# NEW_MEIN.net
KiCad netlist of a schematic drawn in EAGLE
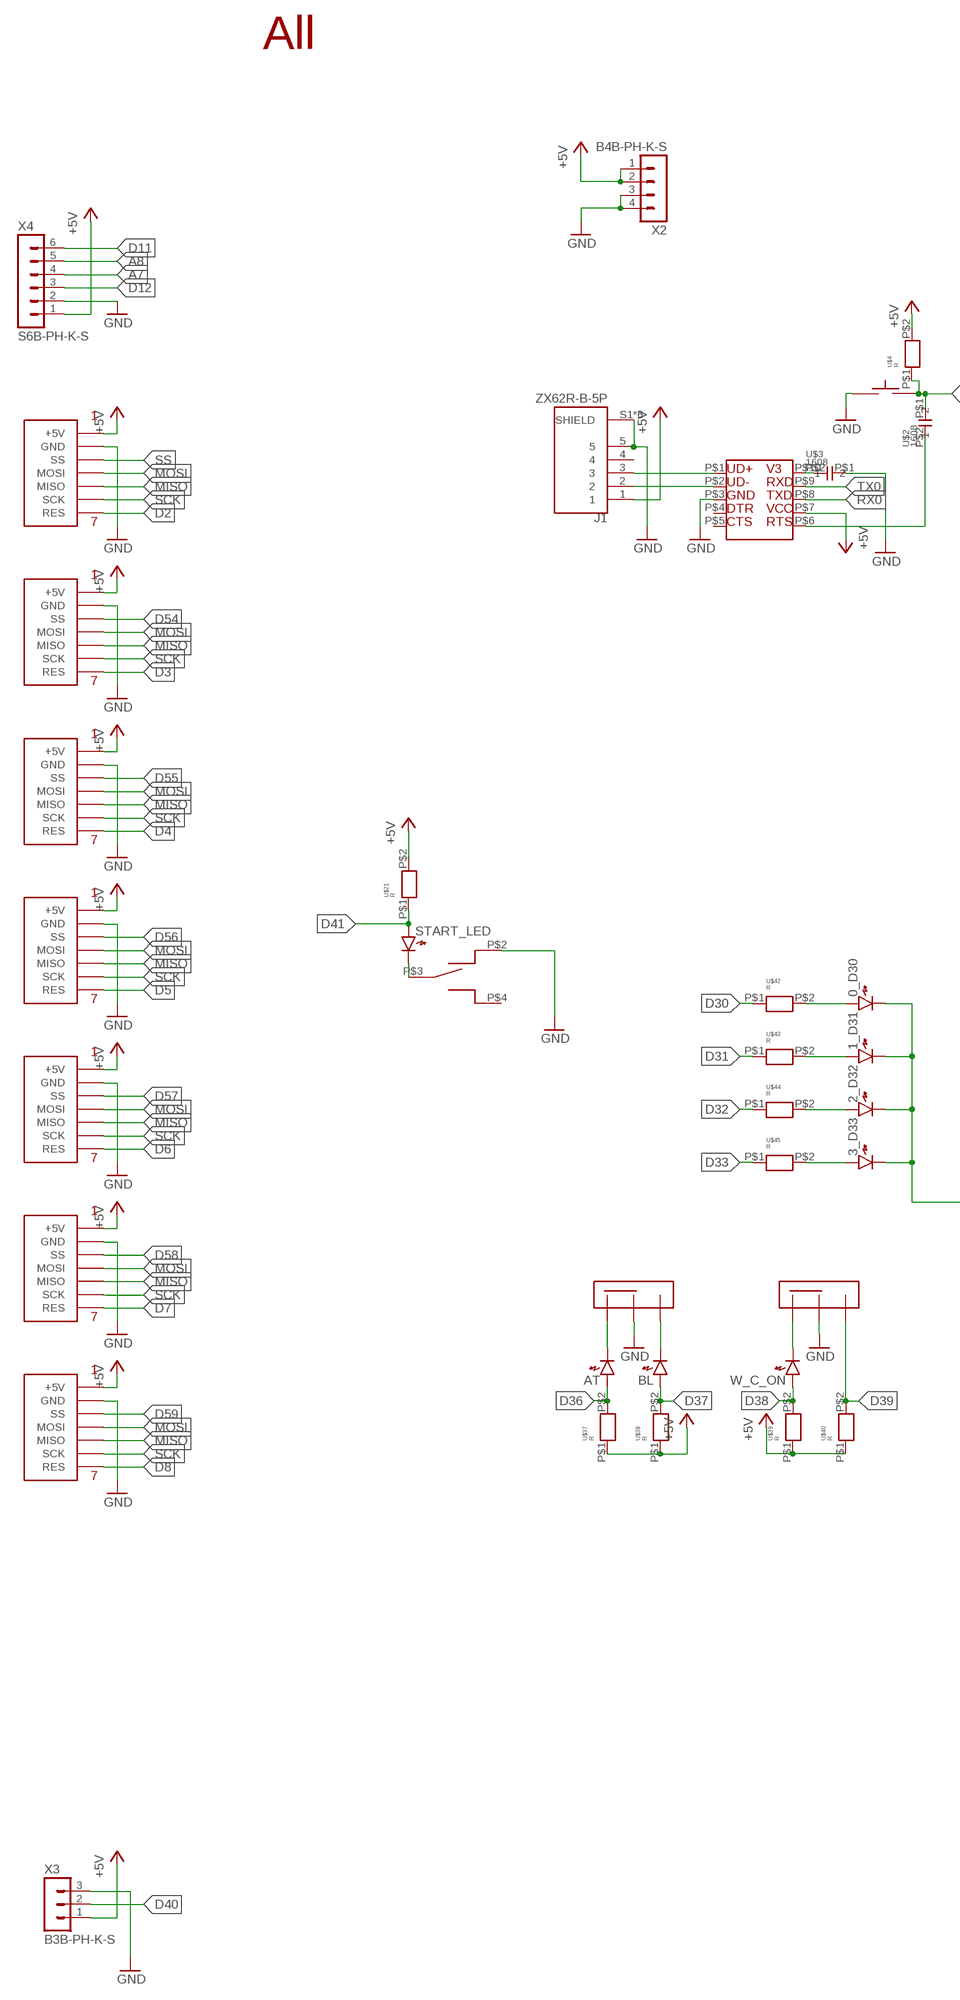
[diagram p0: schematic, sheet 1, part 1 of 2]
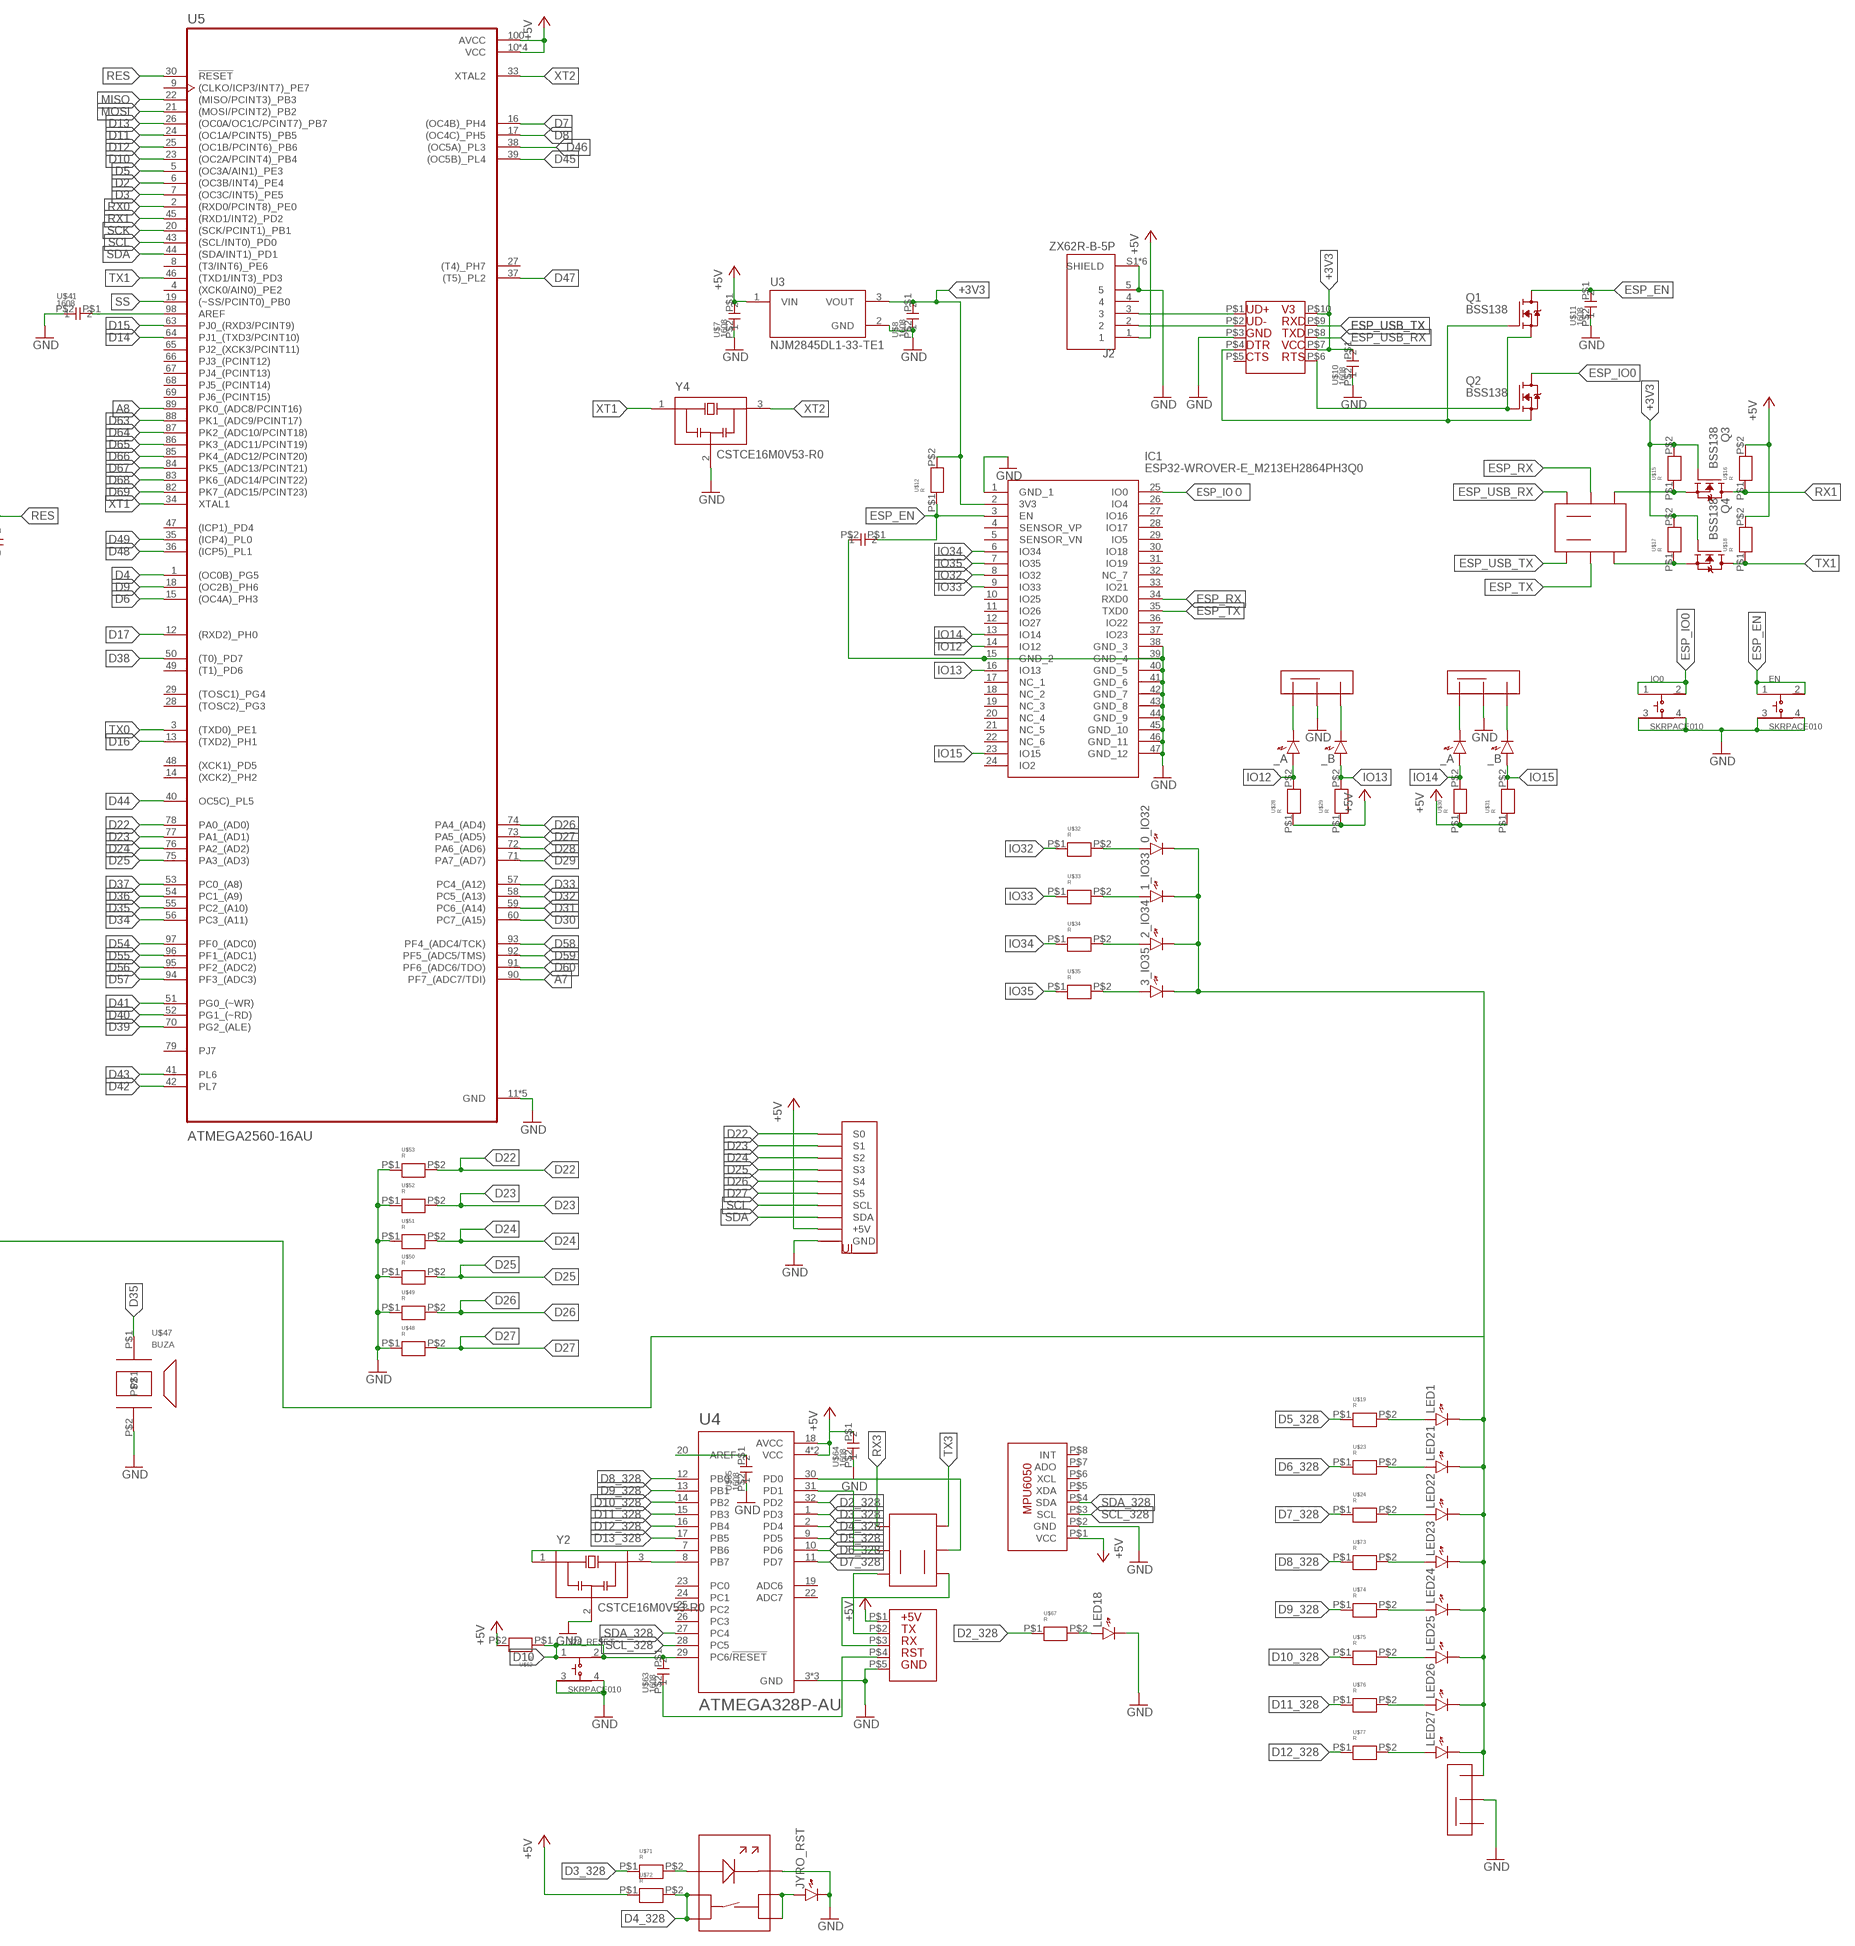
[diagram p1: schematic, sheet 1, part 2 of 2]

(export (version "E")
  (design (tool "Eeschema 10.0.6"))
  (components
    (comp (ref "0_D30")
      (value "LED1608")
      (footprint "eagle-import:LED1608")
      (libsource (lib "eagle-import") (part "LED1608"))
    )
    (comp (ref "0_IO32")
      (value "LED1608")
      (footprint "eagle-import:LED1608")
      (libsource (lib "eagle-import") (part "LED1608"))
    )
    (comp (ref "1_D31")
      (value "LED1608")
      (footprint "eagle-import:LED1608")
      (libsource (lib "eagle-import") (part "LED1608"))
    )
    (comp (ref "1_IO33")
      (value "LED1608")
      (footprint "eagle-import:LED1608")
      (libsource (lib "eagle-import") (part "LED1608"))
    )
    (comp (ref "2_D32")
      (value "LED1608")
      (footprint "eagle-import:LED1608")
      (libsource (lib "eagle-import") (part "LED1608"))
    )
    (comp (ref "2_IO34")
      (value "LED1608")
      (footprint "eagle-import:LED1608")
      (libsource (lib "eagle-import") (part "LED1608"))
    )
    (comp (ref "3_D33")
      (value "LED1608")
      (footprint "eagle-import:LED1608")
      (libsource (lib "eagle-import") (part "LED1608"))
    )
    (comp (ref "3_IO35")
      (value "LED1608")
      (footprint "eagle-import:LED1608")
      (libsource (lib "eagle-import") (part "LED1608"))
    )
    (comp (ref "328_RESET")
      (value "SKRPACE010")
      (footprint "eagle-import:SW_SKRPACE010")
      (fields (field (name "MF") "ALPS"))
      (libsource (lib "eagle-import") (part "SKRPACE010"))
    )
    (comp (ref "AT")
      (value "LED1608")
      (footprint "eagle-import:LED1608")
      (libsource (lib "eagle-import") (part "LED1608"))
    )
    (comp (ref "BL")
      (value "LED1608")
      (footprint "eagle-import:LED1608")
      (libsource (lib "eagle-import") (part "LED1608"))
    )
    (comp (ref "EN")
      (value "SKRPACE010")
      (footprint "eagle-import:SW_SKRPACE010")
      (fields (field (name "MF") "ALPS"))
      (libsource (lib "eagle-import") (part "SKRPACE010"))
    )
    (comp (ref "IC1")
      (value "ESP32-WROVER-E_M213EH2864PH3Q0")
      (footprint "eagle-import:ESP32WROVEREM213EH2864PH3Q0")
      (fields
        (field (name "MANUFACTURER_PART_NUMBER") "ESP32-WROVER-E(M213EH2864PH3Q0)")
        (field (name "MOUSER_PART_NUMBER") "356-ESP32WRVE22864PC")
      )
      (libsource (lib "eagle-import") (part "ESP32-WROVER-E_M213EH2864PH3Q0"))
    )
    (comp (ref "IO0")
      (value "SKRPACE010")
      (footprint "eagle-import:SW_SKRPACE010")
      (fields (field (name "MF") "ALPS"))
      (libsource (lib "eagle-import") (part "SKRPACE010"))
    )
    (comp (ref "J1")
      (value "ZX62R-B-5P")
      (footprint "eagle-import:HRS_ZX62R-B-5P")
      (fields (field (name "MF") "Hirose"))
      (libsource (lib "eagle-import") (part "ZX62R-B-5P"))
    )
    (comp (ref "J2")
      (value "ZX62R-B-5P")
      (footprint "eagle-import:HRS_ZX62R-B-5P")
      (fields (field (name "MF") "Hirose"))
      (libsource (lib "eagle-import") (part "ZX62R-B-5P"))
    )
    (comp (ref "JYRO_RST")
      (value "LED1608")
      (footprint "eagle-import:LED1608")
      (libsource (lib "eagle-import") (part "LED1608"))
    )
    (comp (ref "LED1")
      (value "LED1608")
      (footprint "eagle-import:LED1608")
      (libsource (lib "eagle-import") (part "LED1608"))
    )
    (comp (ref "LED18")
      (value "LED1608")
      (footprint "eagle-import:LED1608")
      (libsource (lib "eagle-import") (part "LED1608"))
    )
    (comp (ref "LED21")
      (value "LED1608")
      (footprint "eagle-import:LED1608")
      (libsource (lib "eagle-import") (part "LED1608"))
    )
    (comp (ref "LED22")
      (value "LED1608")
      (footprint "eagle-import:LED1608")
      (libsource (lib "eagle-import") (part "LED1608"))
    )
    (comp (ref "LED23")
      (value "LED1608")
      (footprint "eagle-import:LED1608")
      (libsource (lib "eagle-import") (part "LED1608"))
    )
    (comp (ref "LED24")
      (value "LED1608")
      (footprint "eagle-import:LED1608")
      (libsource (lib "eagle-import") (part "LED1608"))
    )
    (comp (ref "LED25")
      (value "LED1608")
      (footprint "eagle-import:LED1608")
      (libsource (lib "eagle-import") (part "LED1608"))
    )
    (comp (ref "LED26")
      (value "LED1608")
      (footprint "eagle-import:LED1608")
      (libsource (lib "eagle-import") (part "LED1608"))
    )
    (comp (ref "LED27")
      (value "LED1608")
      (footprint "eagle-import:LED1608")
      (libsource (lib "eagle-import") (part "LED1608"))
    )
    (comp (ref "Q1")
      (value "BSS138")
      (footprint "eagle-import:SOT23")
      (fields (field (name "MF") "Fairchild"))
      (libsource (lib "eagle-import") (part "BSS138"))
    )
    (comp (ref "Q2")
      (value "BSS138")
      (footprint "eagle-import:SOT23")
      (fields (field (name "MF") "Fairchild"))
      (libsource (lib "eagle-import") (part "BSS138"))
    )
    (comp (ref "Q3")
      (value "BSS138")
      (footprint "eagle-import:SOT23")
      (fields (field (name "MF") "Fairchild"))
      (libsource (lib "eagle-import") (part "BSS138"))
    )
    (comp (ref "Q4")
      (value "BSS138")
      (footprint "eagle-import:SOT23")
      (fields (field (name "MF") "Fairchild"))
      (libsource (lib "eagle-import") (part "BSS138"))
    )
    (comp (ref "START_LED")
      (value "LED1608")
      (footprint "eagle-import:LED1608")
      (libsource (lib "eagle-import") (part "LED1608"))
    )
    (comp (ref "U$1")
      (value "CH340K")
      (footprint "eagle-import:CH340K")
      (libsource (lib "eagle-import") (part "CH340K"))
    )
    (comp (ref "U$2")
      (value "1608")
      (footprint "eagle-import:CON")
      (libsource (lib "eagle-import") (part "1608"))
    )
    (comp (ref "U$3")
      (value "1608")
      (footprint "eagle-import:CON")
      (libsource (lib "eagle-import") (part "1608"))
    )
    (comp (ref "U$4") (value "R") (footprint "eagle-import:1608") (libsource (lib "eagle-import") (part "R")))
    (comp (ref "U$5")
      (value "ALL")
      (footprint "eagle-import:ALL")
      (libsource (lib "eagle-import") (part "ALL"))
    )
    (comp (ref "U$6")
      (value "TAKUTO")
      (footprint "eagle-import:12")
      (libsource (lib "eagle-import") (part "TAKUTO"))
    )
    (comp (ref "U$7")
      (value "1608")
      (footprint "eagle-import:CON")
      (libsource (lib "eagle-import") (part "1608"))
    )
    (comp (ref "U$8")
      (value "1608")
      (footprint "eagle-import:CON")
      (libsource (lib "eagle-import") (part "1608"))
    )
    (comp (ref "U$9")
      (value "CH340K")
      (footprint "eagle-import:CH340K")
      (libsource (lib "eagle-import") (part "CH340K"))
    )
    (comp (ref "U$10")
      (value "1608")
      (footprint "eagle-import:CON")
      (libsource (lib "eagle-import") (part "1608"))
    )
    (comp (ref "U$11")
      (value "1608")
      (footprint "eagle-import:CON")
      (libsource (lib "eagle-import") (part "1608"))
    )
    (comp (ref "U$12")
      (value "R")
      (footprint "eagle-import:1608")
      (libsource (lib "eagle-import") (part "R"))
    )
    (comp (ref "U$13")
      (value "1608")
      (footprint "eagle-import:CON")
      (libsource (lib "eagle-import") (part "1608"))
    )
    (comp (ref "U$14")
      (value "2SW")
      (footprint "eagle-import:2SW")
      (libsource (lib "eagle-import") (part "2SW"))
    )
    (comp (ref "U$15")
      (value "R")
      (footprint "eagle-import:1608")
      (libsource (lib "eagle-import") (part "R"))
    )
    (comp (ref "U$16")
      (value "R")
      (footprint "eagle-import:1608")
      (libsource (lib "eagle-import") (part "R"))
    )
    (comp (ref "U$17")
      (value "R")
      (footprint "eagle-import:1608")
      (libsource (lib "eagle-import") (part "R"))
    )
    (comp (ref "U$18")
      (value "R")
      (footprint "eagle-import:1608")
      (libsource (lib "eagle-import") (part "R"))
    )
    (comp (ref "U$19")
      (value "R")
      (footprint "eagle-import:1608")
      (libsource (lib "eagle-import") (part "R"))
    )
    (comp (ref "U$20") (value "S") (footprint "eagle-import:S") (libsource (lib "eagle-import") (part "S")))
    (comp (ref "U$21")
      (value "R")
      (footprint "eagle-import:1608")
      (libsource (lib "eagle-import") (part "R"))
    )
    (comp (ref "U$22")
      (value "SSW")
      (footprint "eagle-import:SSW")
      (libsource (lib "eagle-import") (part "SSW"))
    )
    (comp (ref "U$23")
      (value "R")
      (footprint "eagle-import:1608")
      (libsource (lib "eagle-import") (part "R"))
    )
    (comp (ref "U$24")
      (value "R")
      (footprint "eagle-import:1608")
      (libsource (lib "eagle-import") (part "R"))
    )
    (comp (ref "U$25")
      (value "ジャイロ")
      (footprint "eagle-import:ジャイロ")
      (libsource (lib "eagle-import") (part "ジャイロ"))
    )
    (comp (ref "U$26")
      (value "SSW")
      (footprint "eagle-import:SSW")
      (libsource (lib "eagle-import") (part "SSW"))
    )
    (comp (ref "U$27")
      (value "SSW")
      (footprint "eagle-import:SSW")
      (libsource (lib "eagle-import") (part "SSW"))
    )
    (comp (ref "U$28")
      (value "R")
      (footprint "eagle-import:1608")
      (libsource (lib "eagle-import") (part "R"))
    )
    (comp (ref "U$29")
      (value "R")
      (footprint "eagle-import:1608")
      (libsource (lib "eagle-import") (part "R"))
    )
    (comp (ref "U$30")
      (value "R")
      (footprint "eagle-import:1608")
      (libsource (lib "eagle-import") (part "R"))
    )
    (comp (ref "U$31")
      (value "R")
      (footprint "eagle-import:1608")
      (libsource (lib "eagle-import") (part "R"))
    )
    (comp (ref "U$32")
      (value "R")
      (footprint "eagle-import:1608")
      (libsource (lib "eagle-import") (part "R"))
    )
    (comp (ref "U$33")
      (value "R")
      (footprint "eagle-import:1608")
      (libsource (lib "eagle-import") (part "R"))
    )
    (comp (ref "U$34")
      (value "R")
      (footprint "eagle-import:1608")
      (libsource (lib "eagle-import") (part "R"))
    )
    (comp (ref "U$35")
      (value "R")
      (footprint "eagle-import:1608")
      (libsource (lib "eagle-import") (part "R"))
    )
    (comp (ref "U$36")
      (value "SSW")
      (footprint "eagle-import:SSW")
      (libsource (lib "eagle-import") (part "SSW"))
    )
    (comp (ref "U$37")
      (value "R")
      (footprint "eagle-import:1608")
      (libsource (lib "eagle-import") (part "R"))
    )
    (comp (ref "U$38")
      (value "R")
      (footprint "eagle-import:1608")
      (libsource (lib "eagle-import") (part "R"))
    )
    (comp (ref "U$39")
      (value "R")
      (footprint "eagle-import:1608")
      (libsource (lib "eagle-import") (part "R"))
    )
    (comp (ref "U$40")
      (value "R")
      (footprint "eagle-import:1608")
      (libsource (lib "eagle-import") (part "R"))
    )
    (comp (ref "U$41")
      (value "1608")
      (footprint "eagle-import:CON")
      (libsource (lib "eagle-import") (part "1608"))
    )
    (comp (ref "U$42")
      (value "R")
      (footprint "eagle-import:1608")
      (libsource (lib "eagle-import") (part "R"))
    )
    (comp (ref "U$43")
      (value "R")
      (footprint "eagle-import:1608")
      (libsource (lib "eagle-import") (part "R"))
    )
    (comp (ref "U$44")
      (value "R")
      (footprint "eagle-import:1608")
      (libsource (lib "eagle-import") (part "R"))
    )
    (comp (ref "U$45")
      (value "R")
      (footprint "eagle-import:1608")
      (libsource (lib "eagle-import") (part "R"))
    )
    (comp (ref "U$47")
      (value "BUZA")
      (footprint "eagle-import:BUZA")
      (libsource (lib "eagle-import") (part "BUZA"))
    )
    (comp (ref "U$48")
      (value "R")
      (footprint "eagle-import:1608")
      (libsource (lib "eagle-import") (part "R"))
    )
    (comp (ref "U$49")
      (value "R")
      (footprint "eagle-import:1608")
      (libsource (lib "eagle-import") (part "R"))
    )
    (comp (ref "U$50")
      (value "R")
      (footprint "eagle-import:1608")
      (libsource (lib "eagle-import") (part "R"))
    )
    (comp (ref "U$51")
      (value "R")
      (footprint "eagle-import:1608")
      (libsource (lib "eagle-import") (part "R"))
    )
    (comp (ref "U$52")
      (value "R")
      (footprint "eagle-import:1608")
      (libsource (lib "eagle-import") (part "R"))
    )
    (comp (ref "U$53")
      (value "R")
      (footprint "eagle-import:1608")
      (libsource (lib "eagle-import") (part "R"))
    )
    (comp (ref "U$54")
      (value "SPI")
      (footprint "eagle-import:SPI")
      (libsource (lib "eagle-import") (part "SPI"))
    )
    (comp (ref "U$55")
      (value "SPI")
      (footprint "eagle-import:SPI")
      (libsource (lib "eagle-import") (part "SPI"))
    )
    (comp (ref "U$56")
      (value "SPI")
      (footprint "eagle-import:SPI")
      (libsource (lib "eagle-import") (part "SPI"))
    )
    (comp (ref "U$57")
      (value "SPI")
      (footprint "eagle-import:SPI")
      (libsource (lib "eagle-import") (part "SPI"))
    )
    (comp (ref "U$58")
      (value "SPI")
      (footprint "eagle-import:SPI")
      (libsource (lib "eagle-import") (part "SPI"))
    )
    (comp (ref "U$59")
      (value "SPI")
      (footprint "eagle-import:SPI")
      (libsource (lib "eagle-import") (part "SPI"))
    )
    (comp (ref "U$60")
      (value "SPI")
      (footprint "eagle-import:SPI")
      (libsource (lib "eagle-import") (part "SPI"))
    )
    (comp (ref "U$62")
      (value "R")
      (footprint "eagle-import:1608")
      (libsource (lib "eagle-import") (part "R"))
    )
    (comp (ref "U$63")
      (value "1608")
      (footprint "eagle-import:CON")
      (libsource (lib "eagle-import") (part "1608"))
    )
    (comp (ref "U$64")
      (value "1608")
      (footprint "eagle-import:CON")
      (libsource (lib "eagle-import") (part "1608"))
    )
    (comp (ref "U$65")
      (value "1608")
      (footprint "eagle-import:CON")
      (libsource (lib "eagle-import") (part "1608"))
    )
    (comp (ref "U$66")
      (value "SI")
      (footprint "eagle-import:SI")
      (libsource (lib "eagle-import") (part "SI"))
    )
    (comp (ref "U$67")
      (value "R")
      (footprint "eagle-import:1608")
      (libsource (lib "eagle-import") (part "R"))
    )
    (comp (ref "U$68")
      (value "UI")
      (footprint "eagle-import:UI")
      (libsource (lib "eagle-import") (part "UI"))
    )
    (comp (ref "U$69")
      (value "2SW")
      (footprint "eagle-import:2SW")
      (libsource (lib "eagle-import") (part "2SW"))
    )
    (comp (ref "U$70")
      (value "SWLED")
      (footprint "eagle-import:SWLED")
      (libsource (lib "eagle-import") (part "SWLED"))
    )
    (comp (ref "U$71")
      (value "R")
      (footprint "eagle-import:1608")
      (libsource (lib "eagle-import") (part "R"))
    )
    (comp (ref "U$72")
      (value "R")
      (footprint "eagle-import:1608")
      (libsource (lib "eagle-import") (part "R"))
    )
    (comp (ref "U$73")
      (value "R")
      (footprint "eagle-import:1608")
      (libsource (lib "eagle-import") (part "R"))
    )
    (comp (ref "U$74")
      (value "R")
      (footprint "eagle-import:1608")
      (libsource (lib "eagle-import") (part "R"))
    )
    (comp (ref "U$75")
      (value "R")
      (footprint "eagle-import:1608")
      (libsource (lib "eagle-import") (part "R"))
    )
    (comp (ref "U$76")
      (value "R")
      (footprint "eagle-import:1608")
      (libsource (lib "eagle-import") (part "R"))
    )
    (comp (ref "U$77")
      (value "R")
      (footprint "eagle-import:1608")
      (libsource (lib "eagle-import") (part "R"))
    )
    (comp (ref "U$78")
      (value "SSW")
      (footprint "eagle-import:SSW")
      (libsource (lib "eagle-import") (part "SSW"))
    )
    (comp (ref "U3")
      (value "NJM2845DL1-33-TE1")
      (footprint "eagle-import:DPAK228P968X238-4N")
      (fields (field (name "MF") "NJR Corporation/NJRC"))
      (libsource (lib "eagle-import") (part "NJM2845DL1-33-TE1"))
    )
    (comp (ref "U4")
      (value "ATMEGA328P-AU")
      (footprint "eagle-import:QFP80P900X900X120-32N")
      (fields (field (name "MF") "Microchip Technology"))
      (libsource (lib "eagle-import") (part "ATMEGA328P-AU"))
    )
    (comp (ref "U5")
      (value "ATMEGA2560-16AU")
      (footprint "eagle-import:QFP50P1600X1600X120-100N")
      (fields (field (name "MF") "Microchip Technology"))
      (libsource (lib "eagle-import") (part "ATMEGA2560-16AU"))
    )
    (comp (ref "W_C_ON")
      (value "LED1608")
      (footprint "eagle-import:LED1608")
      (libsource (lib "eagle-import") (part "LED1608"))
    )
    (comp (ref "X2")
      (value "B4B-PH-K-S")
      (footprint "eagle-import:B4B-PH-K-S")
      (libsource (lib "eagle-import") (part "B4B-PH-K-S"))
    )
    (comp (ref "X3")
      (value "B3B-PH-K-S")
      (footprint "eagle-import:B3B-PH-K-S")
      (libsource (lib "eagle-import") (part "B3B-PH-K-S"))
    )
    (comp (ref "X4")
      (value "S6B-PH-K-S")
      (footprint "eagle-import:S6B-PH-K-S")
      (libsource (lib "eagle-import") (part "S6B-PH-K-S"))
    )
    (comp (ref "Y2")
      (value "CSTCE16M0V53-R0")
      (footprint "eagle-import:OSC_CSTCE16M0V53-R0")
      (fields (field (name "MANUFACTURER") "Murata"))
      (libsource (lib "eagle-import") (part "CSTCE16M0V53-R0"))
    )
    (comp (ref "Y4")
      (value "CSTCE16M0V53-R0")
      (footprint "eagle-import:OSC_CSTCE16M0V53-R0")
      (fields (field (name "MANUFACTURER") "Murata"))
      (libsource (lib "eagle-import") (part "CSTCE16M0V53-R0"))
    )
    (comp (ref "Ⅰ_A")
      (value "LED1608")
      (footprint "eagle-import:LED1608")
      (libsource (lib "eagle-import") (part "LED1608"))
    )
    (comp (ref "Ⅰ_B")
      (value "LED1608")
      (footprint "eagle-import:LED1608")
      (libsource (lib "eagle-import") (part "LED1608"))
    )
    (comp (ref "Ⅱ_A")
      (value "LED1608")
      (footprint "eagle-import:LED1608")
      (libsource (lib "eagle-import") (part "LED1608"))
    )
    (comp (ref "Ⅱ_B")
      (value "LED1608")
      (footprint "eagle-import:LED1608")
      (libsource (lib "eagle-import") (part "LED1608"))
    )
  )
  (nets
    (net (code "1") (name "+3V3") (class "Default")
      (node (ref "IC1") (pin "2") (pinfunction "3V3_2") (pintype "bidirectional"))
      (node (ref "Q3") (pin "1") (pinfunction "G_1") (pintype "passive"))
      (node (ref "Q4") (pin "1") (pinfunction "G_1") (pintype "passive"))
      (node (ref "U$10") (pin "P$1") (pinfunction "1_P$1") (pintype "bidirectional"))
      (node (ref "U$12") (pin "P$2") (pinfunction "P$2_P$2") (pintype "bidirectional"))
      (node (ref "U$15") (pin "P$2") (pinfunction "P$2_P$2") (pintype "bidirectional"))
      (node (ref "U$17") (pin "P$2") (pinfunction "P$2_P$2") (pintype "bidirectional"))
      (node (ref "U$8") (pin "P$1") (pinfunction "1_P$1") (pintype "bidirectional"))
      (node (ref "U$9") (pin "P$10") (pinfunction "P$10_P$10") (pintype "bidirectional"))
      (node (ref "U$9") (pin "P$7") (pinfunction "P$7_P$7") (pintype "bidirectional"))
      (node (ref "U3") (pin "3") (pinfunction "VOUT_3") (pintype "output"))
    )
    (net (code "2") (name "+5V") (class "Default")
      (node (ref "J1") (pin "1") (pinfunction "1_1") (pintype "passive"))
      (node (ref "J2") (pin "1") (pinfunction "1_1") (pintype "passive"))
      (node (ref "U$1") (pin "P$7") (pinfunction "P$7_P$7") (pintype "bidirectional"))
      (node (ref "U$16") (pin "P$2") (pinfunction "P$2_P$2") (pintype "bidirectional"))
      (node (ref "U$18") (pin "P$2") (pinfunction "P$2_P$2") (pintype "bidirectional"))
      (node (ref "U$21") (pin "P$2") (pinfunction "P$2_P$2") (pintype "bidirectional"))
      (node (ref "U$25") (pin "P$1") (pinfunction "VCC_P$1") (pintype "bidirectional"))
      (node (ref "U$28") (pin "P$1") (pinfunction "P$1_P$1") (pintype "bidirectional"))
      (node (ref "U$29") (pin "P$1") (pinfunction "P$1_P$1") (pintype "bidirectional"))
      (node (ref "U$30") (pin "P$1") (pinfunction "P$1_P$1") (pintype "bidirectional"))
      (node (ref "U$31") (pin "P$1") (pinfunction "P$1_P$1") (pintype "bidirectional"))
      (node (ref "U$37") (pin "P$1") (pinfunction "P$1_P$1") (pintype "bidirectional"))
      (node (ref "U$38") (pin "P$1") (pinfunction "P$1_P$1") (pintype "bidirectional"))
      (node (ref "U$39") (pin "P$1") (pinfunction "P$1_P$1") (pintype "bidirectional"))
      (node (ref "U$4") (pin "P$2") (pinfunction "P$2_P$2") (pintype "bidirectional"))
      (node (ref "U$40") (pin "P$1") (pinfunction "P$1_P$1") (pintype "bidirectional"))
      (node (ref "U$54") (pin "P$1") (pinfunction "+5V_P$1") (pintype "bidirectional"))
      (node (ref "U$55") (pin "P$1") (pinfunction "+5V_P$1") (pintype "bidirectional"))
      (node (ref "U$56") (pin "P$1") (pinfunction "+5V_P$1") (pintype "bidirectional"))
      (node (ref "U$57") (pin "P$1") (pinfunction "+5V_P$1") (pintype "bidirectional"))
      (node (ref "U$58") (pin "P$1") (pinfunction "+5V_P$1") (pintype "bidirectional"))
      (node (ref "U$59") (pin "P$1") (pinfunction "+5V_P$1") (pintype "bidirectional"))
      (node (ref "U$60") (pin "P$1") (pinfunction "+5V_P$1") (pintype "bidirectional"))
      (node (ref "U$62") (pin "P$2") (pinfunction "P$2_P$2") (pintype "bidirectional"))
      (node (ref "U$64") (pin "P$1") (pinfunction "1_P$1") (pintype "bidirectional"))
      (node (ref "U$66") (pin "P$1") (pinfunction "P$1_P$1") (pintype "bidirectional"))
      (node (ref "U$68") (pin "P$1") (pinfunction "+5V_P$1") (pintype "bidirectional"))
      (node (ref "U$7") (pin "P$1") (pinfunction "1_P$1") (pintype "bidirectional"))
      (node (ref "U$72") (pin "P$1") (pinfunction "P$1_P$1") (pintype "bidirectional"))
      (node (ref "U3") (pin "1") (pinfunction "VIN_1") (pintype "input"))
      (node (ref "U4") (pin "18") (pinfunction "AVCC_18") (pintype "power_in"))
      (node (ref "U4") (pin "4") (pinfunction "VCC_4") (pintype "power_in"))
      (node (ref "U4") (pin "6") (pinfunction "VCC_6") (pintype "power_in"))
      (node (ref "U5") (pin "10") (pinfunction "VCC_10") (pintype "power_in"))
      (node (ref "U5") (pin "100") (pinfunction "AVCC_100") (pintype "power_in"))
      (node (ref "U5") (pin "31") (pinfunction "VCC_31") (pintype "power_in"))
      (node (ref "U5") (pin "61") (pinfunction "VCC_61") (pintype "power_in"))
      (node (ref "U5") (pin "80") (pinfunction "VCC_80") (pintype "power_in"))
      (node (ref "X2") (pin "1") (pinfunction "1_1") (pintype "passive"))
      (node (ref "X2") (pin "2") (pinfunction "2_2") (pintype "passive"))
      (node (ref "X3") (pin "1") (pinfunction "1_1") (pintype "passive"))
      (node (ref "X4") (pin "1") (pinfunction "1_1") (pintype "passive"))
    )
    (net (code "3") (name "A7") (class "Default")
      (node (ref "U5") (pin "90") (pinfunction "PF7_(ADC7/TDI)_90") (pintype "bidirectional"))
      (node (ref "X4") (pin "4") (pinfunction "4_4") (pintype "passive"))
    )
    (net (code "4") (name "A8") (class "Default")
      (node (ref "U5") (pin "89") (pinfunction "PK0_(ADC8/PCINT16)_89") (pintype "input"))
      (node (ref "X4") (pin "5") (pinfunction "5_5") (pintype "passive"))
    )
    (net (code "5") (name "D2") (class "Default")
      (node (ref "U$54") (pin "P$7") (pinfunction "RES_P$7") (pintype "bidirectional"))
      (node (ref "U5") (pin "6") (pinfunction "(OC3B/INT4)_PE4_6") (pintype "input"))
    )
    (net (code "6") (name "D2_328") (class "Default")
      (node (ref "U$67") (pin "P$1") (pinfunction "P$1_P$1") (pintype "bidirectional"))
      (node (ref "U4") (pin "32") (pinfunction "PD2_32") (pintype "bidirectional"))
    )
    (net (code "7") (name "D3") (class "Default")
      (node (ref "U$55") (pin "P$7") (pinfunction "RES_P$7") (pintype "bidirectional"))
      (node (ref "U5") (pin "7") (pinfunction "(OC3C/INT5)_PE5_7") (pintype "input"))
    )
    (net (code "8") (name "D3_328") (class "Default")
      (node (ref "U$71") (pin "P$1") (pinfunction "P$1_P$1") (pintype "bidirectional"))
      (node (ref "U4") (pin "1") (pinfunction "PD3_1") (pintype "bidirectional"))
    )
    (net (code "9") (name "D4") (class "Default")
      (node (ref "U$56") (pin "P$7") (pinfunction "RES_P$7") (pintype "bidirectional"))
      (node (ref "U5") (pin "1") (pinfunction "(OC0B)_PG5_1") (pintype "bidirectional"))
    )
    (net (code "10") (name "D4_328") (class "Default")
      (node (ref "U$70") (pin "1") (pinfunction "1_1") (pintype "bidirectional"))
      (node (ref "U$70") (pin "2") (pinfunction "2_2") (pintype "bidirectional"))
      (node (ref "U$72") (pin "P$2") (pinfunction "P$2_P$2") (pintype "bidirectional"))
      (node (ref "U4") (pin "2") (pinfunction "PD4_2") (pintype "bidirectional"))
    )
    (net (code "11") (name "D5") (class "Default")
      (node (ref "U$57") (pin "P$7") (pinfunction "RES_P$7") (pintype "bidirectional"))
      (node (ref "U5") (pin "5") (pinfunction "(OC3A/AIN1)_PE3_5") (pintype "input"))
    )
    (net (code "12") (name "D5_328") (class "Default")
      (node (ref "U$19") (pin "P$1") (pinfunction "P$1_P$1") (pintype "bidirectional"))
      (node (ref "U4") (pin "9") (pinfunction "PD5_9") (pintype "bidirectional"))
    )
    (net (code "13") (name "D6") (class "Default")
      (node (ref "U$58") (pin "P$7") (pinfunction "RES_P$7") (pintype "bidirectional"))
      (node (ref "U5") (pin "15") (pinfunction "(OC4A)_PH3_15") (pintype "bidirectional"))
    )
    (net (code "14") (name "D6_328") (class "Default")
      (node (ref "U$23") (pin "P$1") (pinfunction "P$1_P$1") (pintype "bidirectional"))
      (node (ref "U4") (pin "10") (pinfunction "PD6_10") (pintype "bidirectional"))
    )
    (net (code "15") (name "D7") (class "Default")
      (node (ref "U$59") (pin "P$7") (pinfunction "RES_P$7") (pintype "bidirectional"))
      (node (ref "U5") (pin "16") (pinfunction "(OC4B)_PH4_16") (pintype "bidirectional"))
    )
    (net (code "16") (name "D7_328") (class "Default")
      (node (ref "U$24") (pin "P$1") (pinfunction "P$1_P$1") (pintype "bidirectional"))
      (node (ref "U4") (pin "11") (pinfunction "PD7_11") (pintype "bidirectional"))
    )
    (net (code "17") (name "D8") (class "Default")
      (node (ref "U$60") (pin "P$7") (pinfunction "RES_P$7") (pintype "bidirectional"))
      (node (ref "U5") (pin "17") (pinfunction "(OC4C)_PH5_17") (pintype "bidirectional"))
    )
    (net (code "18") (name "D8_328") (class "Default")
      (node (ref "U$73") (pin "P$1") (pinfunction "P$1_P$1") (pintype "bidirectional"))
      (node (ref "U4") (pin "12") (pinfunction "PB0_12") (pintype "bidirectional"))
    )
    (net (code "19") (name "D9") (class "Default")
      (node (ref "U5") (pin "18") (pinfunction "(OC2B)_PH6_18") (pintype "bidirectional"))
    )
    (net (code "20") (name "D9_328") (class "Default")
      (node (ref "U$74") (pin "P$1") (pinfunction "P$1_P$1") (pintype "bidirectional"))
      (node (ref "U4") (pin "13") (pinfunction "PB1_13") (pintype "bidirectional"))
    )
    (net (code "21") (name "D10") (class "Default")
      (node (ref "328_RESET") (pin "1") (pinfunction "1_1") (pintype "bidirectional"))
      (node (ref "328_RESET") (pin "2") (pinfunction "2_2") (pintype "bidirectional"))
      (node (ref "U$62") (pin "P$1") (pinfunction "P$1_P$1") (pintype "bidirectional"))
      (node (ref "U$63") (pin "P$1") (pinfunction "1_P$1") (pintype "bidirectional"))
      (node (ref "U4") (pin "29") (pinfunction "PC6/~{RESET}_29") (pintype "bidirectional"))
      (node (ref "U5") (pin "23") (pinfunction "(OC2A/PCINT4)_PB4_23") (pintype "input"))
    )
    (net (code "22") (name "D10_328") (class "Default")
      (node (ref "U$75") (pin "P$1") (pinfunction "P$1_P$1") (pintype "bidirectional"))
      (node (ref "U4") (pin "14") (pinfunction "PB2_14") (pintype "bidirectional"))
    )
    (net (code "23") (name "D11") (class "Default")
      (node (ref "U5") (pin "24") (pinfunction "(OC1A/PCINT5)_PB5_24") (pintype "input"))
      (node (ref "X4") (pin "6") (pinfunction "6_6") (pintype "passive"))
    )
    (net (code "24") (name "D11_328") (class "Default")
      (node (ref "U$76") (pin "P$1") (pinfunction "P$1_P$1") (pintype "bidirectional"))
      (node (ref "U4") (pin "15") (pinfunction "PB3_15") (pintype "bidirectional"))
    )
    (net (code "25") (name "D12") (class "Default")
      (node (ref "U5") (pin "25") (pinfunction "(OC1B/PCINT6)_PB6_25") (pintype "input"))
      (node (ref "X4") (pin "3") (pinfunction "3_3") (pintype "passive"))
    )
    (net (code "26") (name "D12_328") (class "Default")
      (node (ref "U$77") (pin "P$1") (pinfunction "P$1_P$1") (pintype "bidirectional"))
      (node (ref "U4") (pin "16") (pinfunction "PB4_16") (pintype "bidirectional"))
    )
    (net (code "27") (name "D13") (class "Default")
      (node (ref "U5") (pin "26") (pinfunction "(OC0A/OC1C/PCINT7)_PB7_26") (pintype "input"))
    )
    (net (code "28") (name "D13_328") (class "Default")
      (node (ref "U4") (pin "17") (pinfunction "PB5_17") (pintype "bidirectional"))
    )
    (net (code "29") (name "D14") (class "Default")
      (node (ref "U5") (pin "64") (pinfunction "PJ1_(TXD3/PCINT10)_64") (pintype "input"))
    )
    (net (code "30") (name "D15") (class "Default")
      (node (ref "U5") (pin "63") (pinfunction "PJ0_(RXD3/PCINT9)_63") (pintype "input"))
    )
    (net (code "31") (name "D16") (class "Default")
      (node (ref "U5") (pin "13") (pinfunction "(TXD2)_PH1_13") (pintype "bidirectional"))
    )
    (net (code "32") (name "D17") (class "Default")
      (node (ref "U5") (pin "12") (pinfunction "(RXD2)_PH0_12") (pintype "bidirectional"))
    )
    (net (code "33") (name "D22") (class "Default")
      (node (ref "U$53") (pin "P$2") (pinfunction "P$2_P$2") (pintype "bidirectional"))
      (node (ref "U$68") (pin "P$3") (pinfunction "S0_P$3") (pintype "bidirectional"))
      (node (ref "U5") (pin "78") (pinfunction "PA0_(AD0)_78") (pintype "bidirectional"))
    )
    (net (code "34") (name "D23") (class "Default")
      (node (ref "U$52") (pin "P$2") (pinfunction "P$2_P$2") (pintype "bidirectional"))
      (node (ref "U$68") (pin "P$4") (pinfunction "S1_P$4") (pintype "bidirectional"))
      (node (ref "U5") (pin "77") (pinfunction "PA1_(AD1)_77") (pintype "bidirectional"))
    )
    (net (code "35") (name "D24") (class "Default")
      (node (ref "U$51") (pin "P$2") (pinfunction "P$2_P$2") (pintype "bidirectional"))
      (node (ref "U$68") (pin "P$5") (pinfunction "S2_P$5") (pintype "bidirectional"))
      (node (ref "U5") (pin "76") (pinfunction "PA2_(AD2)_76") (pintype "bidirectional"))
    )
    (net (code "36") (name "D25") (class "Default")
      (node (ref "U$50") (pin "P$2") (pinfunction "P$2_P$2") (pintype "bidirectional"))
      (node (ref "U$68") (pin "P$6") (pinfunction "S3_P$6") (pintype "bidirectional"))
      (node (ref "U5") (pin "75") (pinfunction "PA3_(AD3)_75") (pintype "bidirectional"))
    )
    (net (code "37") (name "D26") (class "Default")
      (node (ref "U$49") (pin "P$2") (pinfunction "P$2_P$2") (pintype "bidirectional"))
      (node (ref "U$68") (pin "P$7") (pinfunction "S4_P$7") (pintype "bidirectional"))
      (node (ref "U5") (pin "74") (pinfunction "PA4_(AD4)_74") (pintype "bidirectional"))
    )
    (net (code "38") (name "D27") (class "Default")
      (node (ref "U$48") (pin "P$2") (pinfunction "P$2_P$2") (pintype "bidirectional"))
      (node (ref "U$68") (pin "P$8") (pinfunction "S5_P$8") (pintype "bidirectional"))
      (node (ref "U5") (pin "73") (pinfunction "PA5_(AD5)_73") (pintype "bidirectional"))
    )
    (net (code "39") (name "D28") (class "Default")
      (node (ref "U5") (pin "72") (pinfunction "PA6_(AD6)_72") (pintype "bidirectional"))
    )
    (net (code "40") (name "D29") (class "Default")
      (node (ref "U5") (pin "71") (pinfunction "PA7_(AD7)_71") (pintype "bidirectional"))
    )
    (net (code "41") (name "D30") (class "Default")
      (node (ref "U$42") (pin "P$1") (pinfunction "P$1_P$1") (pintype "bidirectional"))
      (node (ref "U5") (pin "60") (pinfunction "PC7_(A15)_60") (pintype "bidirectional"))
    )
    (net (code "42") (name "D31") (class "Default")
      (node (ref "U$43") (pin "P$1") (pinfunction "P$1_P$1") (pintype "bidirectional"))
      (node (ref "U5") (pin "59") (pinfunction "PC6_(A14)_59") (pintype "bidirectional"))
    )
    (net (code "43") (name "D32") (class "Default")
      (node (ref "U$44") (pin "P$1") (pinfunction "P$1_P$1") (pintype "bidirectional"))
      (node (ref "U5") (pin "58") (pinfunction "PC5_(A13)_58") (pintype "bidirectional"))
    )
    (net (code "44") (name "D33") (class "Default")
      (node (ref "U$45") (pin "P$1") (pinfunction "P$1_P$1") (pintype "bidirectional"))
      (node (ref "U5") (pin "57") (pinfunction "PC4_(A12)_57") (pintype "bidirectional"))
    )
    (net (code "45") (name "D34") (class "Default")
      (node (ref "U5") (pin "56") (pinfunction "PC3_(A11)_56") (pintype "bidirectional"))
    )
    (net (code "46") (name "D35") (class "Default")
      (node (ref "U$47") (pin "P$1") (pinfunction "P$1_P$1") (pintype "bidirectional"))
      (node (ref "U5") (pin "55") (pinfunction "PC2_(A10)_55") (pintype "bidirectional"))
    )
    (net (code "47") (name "D36") (class "Default")
      (node (ref "AT") (pin "A") (pinfunction "A_A") (pintype "passive"))
      (node (ref "U$37") (pin "P$2") (pinfunction "P$2_P$2") (pintype "bidirectional"))
      (node (ref "U5") (pin "54") (pinfunction "PC1_(A9)_54") (pintype "bidirectional"))
    )
    (net (code "48") (name "D37") (class "Default")
      (node (ref "BL") (pin "A") (pinfunction "A_A") (pintype "passive"))
      (node (ref "U$38") (pin "P$2") (pinfunction "P$2_P$2") (pintype "bidirectional"))
      (node (ref "U5") (pin "53") (pinfunction "PC0_(A8)_53") (pintype "bidirectional"))
    )
    (net (code "49") (name "D38") (class "Default")
      (node (ref "U$39") (pin "P$2") (pinfunction "P$2_P$2") (pintype "bidirectional"))
      (node (ref "U5") (pin "50") (pinfunction "(T0)_PD7_50") (pintype "bidirectional"))
      (node (ref "W_C_ON") (pin "A") (pinfunction "A_A") (pintype "passive"))
    )
    (net (code "50") (name "D39") (class "Default")
      (node (ref "U$36") (pin "P$2") (pinfunction "P$3_P$2") (pintype "bidirectional"))
      (node (ref "U$40") (pin "P$2") (pinfunction "P$2_P$2") (pintype "bidirectional"))
      (node (ref "U5") (pin "70") (pinfunction "PG2_(ALE)_70") (pintype "bidirectional"))
    )
    (net (code "51") (name "D40") (class "Default")
      (node (ref "U5") (pin "52") (pinfunction "PG1_(~{RD})_52") (pintype "bidirectional"))
      (node (ref "X3") (pin "2") (pinfunction "2_2") (pintype "passive"))
    )
    (net (code "52") (name "D41") (class "Default")
      (node (ref "START_LED") (pin "A") (pinfunction "A_A") (pintype "passive"))
      (node (ref "U$21") (pin "P$1") (pinfunction "P$1_P$1") (pintype "bidirectional"))
      (node (ref "U5") (pin "51") (pinfunction "PG0_(~{WR})_51") (pintype "bidirectional"))
    )
    (net (code "53") (name "D42") (class "Default")
      (node (ref "U5") (pin "42") (pinfunction "PL7_42") (pintype "bidirectional"))
    )
    (net (code "54") (name "D43") (class "Default")
      (node (ref "U5") (pin "41") (pinfunction "PL6_41") (pintype "bidirectional"))
    )
    (net (code "55") (name "D44") (class "Default")
      (node (ref "U5") (pin "40") (pinfunction "OC5C)_PL5_40") (pintype "bidirectional"))
    )
    (net (code "56") (name "D45") (class "Default")
      (node (ref "U5") (pin "39") (pinfunction "(OC5B)_PL4_39") (pintype "bidirectional"))
    )
    (net (code "57") (name "D46") (class "Default")
      (node (ref "U5") (pin "38") (pinfunction "(OC5A)_PL3_38") (pintype "bidirectional"))
    )
    (net (code "58") (name "D47") (class "Default")
      (node (ref "U5") (pin "37") (pinfunction "(T5)_PL2_37") (pintype "bidirectional"))
    )
    (net (code "59") (name "D48") (class "Default")
      (node (ref "U5") (pin "36") (pinfunction "(ICP5)_PL1_36") (pintype "bidirectional"))
    )
    (net (code "60") (name "D49") (class "Default")
      (node (ref "U5") (pin "35") (pinfunction "(ICP4)_PL0_35") (pintype "bidirectional"))
    )
    (net (code "61") (name "D54") (class "Default")
      (node (ref "U$55") (pin "P$3") (pinfunction "SS_P$3") (pintype "bidirectional"))
      (node (ref "U5") (pin "97") (pinfunction "PF0_(ADC0)_97") (pintype "bidirectional"))
    )
    (net (code "62") (name "D55") (class "Default")
      (node (ref "U$56") (pin "P$3") (pinfunction "SS_P$3") (pintype "bidirectional"))
      (node (ref "U5") (pin "96") (pinfunction "PF1_(ADC1)_96") (pintype "bidirectional"))
    )
    (net (code "63") (name "D56") (class "Default")
      (node (ref "U$57") (pin "P$3") (pinfunction "SS_P$3") (pintype "bidirectional"))
      (node (ref "U5") (pin "95") (pinfunction "PF2_(ADC2)_95") (pintype "bidirectional"))
    )
    (net (code "64") (name "D57") (class "Default")
      (node (ref "U$58") (pin "P$3") (pinfunction "SS_P$3") (pintype "bidirectional"))
      (node (ref "U5") (pin "94") (pinfunction "PF3_(ADC3)_94") (pintype "bidirectional"))
    )
    (net (code "65") (name "D58") (class "Default")
      (node (ref "U$59") (pin "P$3") (pinfunction "SS_P$3") (pintype "bidirectional"))
      (node (ref "U5") (pin "93") (pinfunction "PF4_(ADC4/TCK)_93") (pintype "bidirectional"))
    )
    (net (code "66") (name "D59") (class "Default")
      (node (ref "U$60") (pin "P$3") (pinfunction "SS_P$3") (pintype "bidirectional"))
      (node (ref "U5") (pin "92") (pinfunction "PF5_(ADC5/TMS)_92") (pintype "bidirectional"))
    )
    (net (code "67") (name "D60") (class "Default")
      (node (ref "U5") (pin "91") (pinfunction "PF6_(ADC6/TDO)_91") (pintype "bidirectional"))
    )
    (net (code "68") (name "D63") (class "Default")
      (node (ref "U5") (pin "88") (pinfunction "PK1_(ADC9/PCINT17)_88") (pintype "input"))
    )
    (net (code "69") (name "D64") (class "Default")
      (node (ref "U5") (pin "87") (pinfunction "PK2_(ADC10/PCINT18)_87") (pintype "input"))
    )
    (net (code "70") (name "D65") (class "Default")
      (node (ref "U5") (pin "86") (pinfunction "PK3_(ADC11/PCINT19)_86") (pintype "input"))
    )
    (net (code "71") (name "D66") (class "Default")
      (node (ref "U5") (pin "85") (pinfunction "PK4_(ADC12/PCINT20)_85") (pintype "input"))
    )
    (net (code "72") (name "D67") (class "Default")
      (node (ref "U5") (pin "84") (pinfunction "PK5_(ADC13/PCINT21)_84") (pintype "input"))
    )
    (net (code "73") (name "D68") (class "Default")
      (node (ref "U5") (pin "83") (pinfunction "PK6_(ADC14/PCINT22)_83") (pintype "input"))
    )
    (net (code "74") (name "D69") (class "Default")
      (node (ref "U5") (pin "82") (pinfunction "PK7_(ADC15/PCINT23)_82") (pintype "input"))
    )
    (net (code "75") (name "ESP_EN") (class "Default")
      (node (ref "EN") (pin "1") (pinfunction "1_1") (pintype "bidirectional"))
      (node (ref "EN") (pin "2") (pinfunction "2_2") (pintype "bidirectional"))
      (node (ref "IC1") (pin "3") (pinfunction "EN_3") (pintype "bidirectional"))
      (node (ref "Q1") (pin "3") (pinfunction "D_3") (pintype "passive"))
      (node (ref "U$11") (pin "P$1") (pinfunction "1_P$1") (pintype "bidirectional"))
      (node (ref "U$12") (pin "P$1") (pinfunction "P$1_P$1") (pintype "bidirectional"))
      (node (ref "U$13") (pin "P$1") (pinfunction "1_P$1") (pintype "bidirectional"))
    )
    (net (code "76") (name "ESP_IO0") (class "Default")
      (node (ref "IO0") (pin "1") (pinfunction "1_1") (pintype "bidirectional"))
      (node (ref "IO0") (pin "2") (pinfunction "2_2") (pintype "bidirectional"))
      (node (ref "Q2") (pin "3") (pinfunction "D_3") (pintype "passive"))
    )
    (net (code "77") (name "ESP_IO０") (class "Default")
      (node (ref "IC1") (pin "25") (pinfunction "IO0_25") (pintype "bidirectional"))
    )
    (net (code "78") (name "ESP_RX") (class "Default")
      (node (ref "IC1") (pin "34") (pinfunction "RXD0_34") (pintype "bidirectional"))
      (node (ref "U$14") (pin "P$2") (pinfunction "P$2_P$2") (pintype "bidirectional"))
    )
    (net (code "79") (name "ESP_TX") (class "Default")
      (node (ref "IC1") (pin "35") (pinfunction "TXD0_35") (pintype "bidirectional"))
      (node (ref "U$14") (pin "P$5") (pinfunction "P$5_P$5") (pintype "bidirectional"))
    )
    (net (code "80") (name "ESP_USB_RX") (class "Default")
      (node (ref "U$14") (pin "P$1") (pinfunction "P$1_P$1") (pintype "bidirectional"))
      (node (ref "U$9") (pin "P$8") (pinfunction "P$8_P$8") (pintype "bidirectional"))
    )
    (net (code "81") (name "ESP_USB_TX") (class "Default")
      (node (ref "U$14") (pin "P$6") (pinfunction "P$4_P$6") (pintype "bidirectional"))
      (node (ref "U$9") (pin "P$9") (pinfunction "P$9_P$9") (pintype "bidirectional"))
    )
    (net (code "82") (name "GND") (class "Default")
      (node (ref "328_RESET") (pin "3") (pinfunction "3_3") (pintype "bidirectional"))
      (node (ref "328_RESET") (pin "4") (pinfunction "4_4") (pintype "bidirectional"))
      (node (ref "EN") (pin "3") (pinfunction "3_3") (pintype "bidirectional"))
      (node (ref "EN") (pin "4") (pinfunction "4_4") (pintype "bidirectional"))
      (node (ref "IC1") (pin "1") (pinfunction "GND_1_1") (pintype "bidirectional"))
      (node (ref "IC1") (pin "15") (pinfunction "GND_2_15") (pintype "bidirectional"))
      (node (ref "IC1") (pin "38") (pinfunction "GND_3_38") (pintype "bidirectional"))
      (node (ref "IC1") (pin "39") (pinfunction "GND_4_39") (pintype "bidirectional"))
      (node (ref "IC1") (pin "40") (pinfunction "GND_5_40") (pintype "bidirectional"))
      (node (ref "IC1") (pin "41") (pinfunction "GND_6_41") (pintype "bidirectional"))
      (node (ref "IC1") (pin "42") (pinfunction "GND_7_42") (pintype "bidirectional"))
      (node (ref "IC1") (pin "43") (pinfunction "GND_8_43") (pintype "bidirectional"))
      (node (ref "IC1") (pin "44") (pinfunction "GND_9_44") (pintype "bidirectional"))
      (node (ref "IC1") (pin "45") (pinfunction "GND_10_45") (pintype "bidirectional"))
      (node (ref "IC1") (pin "46") (pinfunction "GND_11_46") (pintype "bidirectional"))
      (node (ref "IC1") (pin "47") (pinfunction "GND_12_47") (pintype "bidirectional"))
      (node (ref "IO0") (pin "3") (pinfunction "3_3") (pintype "bidirectional"))
      (node (ref "IO0") (pin "4") (pinfunction "4_4") (pintype "bidirectional"))
      (node (ref "J1") (pin "5") (pinfunction "5_5") (pintype "passive"))
      (node (ref "J1") (pin "S1") (pinfunction "SHIELD_S1") (pintype "passive"))
      (node (ref "J1") (pin "S2") (pinfunction "SHIELD_S2") (pintype "passive"))
      (node (ref "J1") (pin "S3") (pinfunction "SHIELD_S3") (pintype "passive"))
      (node (ref "J1") (pin "S4") (pinfunction "SHIELD_S4") (pintype "passive"))
      (node (ref "J1") (pin "S5") (pinfunction "SHIELD_S5") (pintype "passive"))
      (node (ref "J1") (pin "S6") (pinfunction "SHIELD_S6") (pintype "passive"))
      (node (ref "J2") (pin "5") (pinfunction "5_5") (pintype "passive"))
      (node (ref "J2") (pin "S1") (pinfunction "SHIELD_S1") (pintype "passive"))
      (node (ref "J2") (pin "S2") (pinfunction "SHIELD_S2") (pintype "passive"))
      (node (ref "J2") (pin "S3") (pinfunction "SHIELD_S3") (pintype "passive"))
      (node (ref "J2") (pin "S4") (pinfunction "SHIELD_S4") (pintype "passive"))
      (node (ref "J2") (pin "S5") (pinfunction "SHIELD_S5") (pintype "passive"))
      (node (ref "J2") (pin "S6") (pinfunction "SHIELD_S6") (pintype "passive"))
      (node (ref "JYRO_RST") (pin "K") (pinfunction "K_K") (pintype "passive"))
      (node (ref "LED18") (pin "K") (pinfunction "K_K") (pintype "passive"))
      (node (ref "U$1") (pin "P$3") (pinfunction "P$3_P$3") (pintype "bidirectional"))
      (node (ref "U$10") (pin "P$2") (pinfunction "2_P$2") (pintype "bidirectional"))
      (node (ref "U$11") (pin "P$2") (pinfunction "2_P$2") (pintype "bidirectional"))
      (node (ref "U$13") (pin "P$2") (pinfunction "2_P$2") (pintype "bidirectional"))
      (node (ref "U$20") (pin "P$2") (pinfunction "1_P$2") (pintype "bidirectional"))
      (node (ref "U$22") (pin "P$3") (pinfunction "P$2_P$3") (pintype "bidirectional"))
      (node (ref "U$25") (pin "P$2") (pinfunction "GND_P$2") (pintype "bidirectional"))
      (node (ref "U$26") (pin "P$3") (pinfunction "P$2_P$3") (pintype "bidirectional"))
      (node (ref "U$27") (pin "P$3") (pinfunction "P$2_P$3") (pintype "bidirectional"))
      (node (ref "U$3") (pin "P$1") (pinfunction "1_P$1") (pintype "bidirectional"))
      (node (ref "U$36") (pin "P$3") (pinfunction "P$2_P$3") (pintype "bidirectional"))
      (node (ref "U$41") (pin "P$2") (pinfunction "2_P$2") (pintype "bidirectional"))
      (node (ref "U$47") (pin "P$2") (pinfunction "P$2_P$2") (pintype "bidirectional"))
      (node (ref "U$48") (pin "P$1") (pinfunction "P$1_P$1") (pintype "bidirectional"))
      (node (ref "U$49") (pin "P$1") (pinfunction "P$1_P$1") (pintype "bidirectional"))
      (node (ref "U$50") (pin "P$1") (pinfunction "P$1_P$1") (pintype "bidirectional"))
      (node (ref "U$51") (pin "P$1") (pinfunction "P$1_P$1") (pintype "bidirectional"))
      (node (ref "U$52") (pin "P$1") (pinfunction "P$1_P$1") (pintype "bidirectional"))
      (node (ref "U$53") (pin "P$1") (pinfunction "P$1_P$1") (pintype "bidirectional"))
      (node (ref "U$54") (pin "P$2") (pinfunction "GND_P$2") (pintype "bidirectional"))
      (node (ref "U$55") (pin "P$2") (pinfunction "GND_P$2") (pintype "bidirectional"))
      (node (ref "U$56") (pin "P$2") (pinfunction "GND_P$2") (pintype "bidirectional"))
      (node (ref "U$57") (pin "P$2") (pinfunction "GND_P$2") (pintype "bidirectional"))
      (node (ref "U$58") (pin "P$2") (pinfunction "GND_P$2") (pintype "bidirectional"))
      (node (ref "U$59") (pin "P$2") (pinfunction "GND_P$2") (pintype "bidirectional"))
      (node (ref "U$6") (pin "P$1") (pinfunction "P$1_P$1") (pintype "bidirectional"))
      (node (ref "U$6") (pin "P$4") (pinfunction "P$1_P$4") (pintype "bidirectional"))
      (node (ref "U$60") (pin "P$2") (pinfunction "GND_P$2") (pintype "bidirectional"))
      (node (ref "U$64") (pin "P$2") (pinfunction "2_P$2") (pintype "bidirectional"))
      (node (ref "U$65") (pin "P$2") (pinfunction "2_P$2") (pintype "bidirectional"))
      (node (ref "U$66") (pin "P$5") (pinfunction "P$5_P$5") (pintype "bidirectional"))
      (node (ref "U$68") (pin "P$2") (pinfunction "GND_P$2") (pintype "bidirectional"))
      (node (ref "U$7") (pin "P$2") (pinfunction "2_P$2") (pintype "bidirectional"))
      (node (ref "U$70") (pin "-") (pinfunction "LED-_-") (pintype "bidirectional"))
      (node (ref "U$78") (pin "P$3") (pinfunction "P$2_P$3") (pintype "bidirectional"))
      (node (ref "U$8") (pin "P$2") (pinfunction "2_P$2") (pintype "bidirectional"))
      (node (ref "U$9") (pin "P$3") (pinfunction "P$3_P$3") (pintype "bidirectional"))
      (node (ref "U3") (pin "2") (pinfunction "GND_2") (pintype "power_in"))
      (node (ref "U4") (pin "21") (pinfunction "GND_21") (pintype "power_in"))
      (node (ref "U4") (pin "3") (pinfunction "GND_3") (pintype "power_in"))
      (node (ref "U4") (pin "5") (pinfunction "GND_5") (pintype "power_in"))
      (node (ref "U5") (pin "11") (pinfunction "GND_11") (pintype "power_in"))
      (node (ref "U5") (pin "32") (pinfunction "GND_32") (pintype "power_in"))
      (node (ref "U5") (pin "62") (pinfunction "GND_62") (pintype "power_in"))
      (node (ref "U5") (pin "81") (pinfunction "GND_81") (pintype "power_in"))
      (node (ref "U5") (pin "99") (pinfunction "GND_99") (pintype "power_in"))
      (node (ref "X2") (pin "3") (pinfunction "3_3") (pintype "passive"))
      (node (ref "X2") (pin "4") (pinfunction "4_4") (pintype "passive"))
      (node (ref "X3") (pin "3") (pinfunction "3_3") (pintype "passive"))
      (node (ref "X4") (pin "2") (pinfunction "2_2") (pintype "passive"))
      (node (ref "Y2") (pin "2") (pinfunction "GND_2") (pintype "power_in"))
      (node (ref "Y4") (pin "2") (pinfunction "GND_2") (pintype "power_in"))
    )
    (net (code "83") (name "IO12") (class "Default")
      (node (ref "IC1") (pin "14") (pinfunction "IO12_14") (pintype "bidirectional"))
      (node (ref "U$28") (pin "P$2") (pinfunction "P$2_P$2") (pintype "bidirectional"))
      (node (ref "Ⅰ_A") (pin "A") (pinfunction "A_A") (pintype "passive"))
    )
    (net (code "84") (name "IO13") (class "Default")
      (node (ref "IC1") (pin "16") (pinfunction "IO13_16") (pintype "bidirectional"))
      (node (ref "U$29") (pin "P$2") (pinfunction "P$2_P$2") (pintype "bidirectional"))
      (node (ref "Ⅰ_B") (pin "A") (pinfunction "A_A") (pintype "passive"))
    )
    (net (code "85") (name "IO14") (class "Default")
      (node (ref "IC1") (pin "13") (pinfunction "IO14_13") (pintype "bidirectional"))
      (node (ref "U$30") (pin "P$2") (pinfunction "P$2_P$2") (pintype "bidirectional"))
      (node (ref "Ⅱ_A") (pin "A") (pinfunction "A_A") (pintype "passive"))
    )
    (net (code "86") (name "IO15") (class "Default")
      (node (ref "IC1") (pin "23") (pinfunction "IO15_23") (pintype "bidirectional"))
      (node (ref "U$31") (pin "P$2") (pinfunction "P$2_P$2") (pintype "bidirectional"))
      (node (ref "Ⅱ_B") (pin "A") (pinfunction "A_A") (pintype "passive"))
    )
    (net (code "87") (name "IO32") (class "Default")
      (node (ref "IC1") (pin "8") (pinfunction "IO32_8") (pintype "bidirectional"))
      (node (ref "U$32") (pin "P$1") (pinfunction "P$1_P$1") (pintype "bidirectional"))
    )
    (net (code "88") (name "IO33") (class "Default")
      (node (ref "IC1") (pin "9") (pinfunction "IO33_9") (pintype "bidirectional"))
      (node (ref "U$33") (pin "P$1") (pinfunction "P$1_P$1") (pintype "bidirectional"))
    )
    (net (code "89") (name "IO34") (class "Default")
      (node (ref "IC1") (pin "6") (pinfunction "IO34_6") (pintype "bidirectional"))
      (node (ref "U$34") (pin "P$1") (pinfunction "P$1_P$1") (pintype "bidirectional"))
    )
    (net (code "90") (name "IO35") (class "Default")
      (node (ref "IC1") (pin "7") (pinfunction "IO35_7") (pintype "bidirectional"))
      (node (ref "U$35") (pin "P$1") (pinfunction "P$1_P$1") (pintype "bidirectional"))
    )
    (net (code "91") (name "MISO") (class "Default")
      (node (ref "U$54") (pin "P$5") (pinfunction "MISO_P$5") (pintype "bidirectional"))
      (node (ref "U$55") (pin "P$5") (pinfunction "MISO_P$5") (pintype "bidirectional"))
      (node (ref "U$56") (pin "P$5") (pinfunction "MISO_P$5") (pintype "bidirectional"))
      (node (ref "U$57") (pin "P$5") (pinfunction "MISO_P$5") (pintype "bidirectional"))
      (node (ref "U$58") (pin "P$5") (pinfunction "MISO_P$5") (pintype "bidirectional"))
      (node (ref "U$59") (pin "P$5") (pinfunction "MISO_P$5") (pintype "bidirectional"))
      (node (ref "U$60") (pin "P$5") (pinfunction "MISO_P$5") (pintype "bidirectional"))
      (node (ref "U5") (pin "22") (pinfunction "(MISO/PCINT3)_PB3_22") (pintype "input"))
    )
    (net (code "92") (name "MOSI") (class "Default")
      (node (ref "U$54") (pin "P$4") (pinfunction "MOSI_P$4") (pintype "bidirectional"))
      (node (ref "U$55") (pin "P$4") (pinfunction "MOSI_P$4") (pintype "bidirectional"))
      (node (ref "U$56") (pin "P$4") (pinfunction "MOSI_P$4") (pintype "bidirectional"))
      (node (ref "U$57") (pin "P$4") (pinfunction "MOSI_P$4") (pintype "bidirectional"))
      (node (ref "U$58") (pin "P$4") (pinfunction "MOSI_P$4") (pintype "bidirectional"))
      (node (ref "U$59") (pin "P$4") (pinfunction "MOSI_P$4") (pintype "bidirectional"))
      (node (ref "U$60") (pin "P$4") (pinfunction "MOSI_P$4") (pintype "bidirectional"))
      (node (ref "U5") (pin "21") (pinfunction "(MOSI/PCINT2)_PB2_21") (pintype "input"))
    )
    (net (code "93") (name "Net-(0_D30-PadA)") (class "Default")
      (node (ref "0_D30") (pin "A") (pinfunction "A_A") (pintype "passive"))
      (node (ref "U$42") (pin "P$2") (pinfunction "P$2_P$2") (pintype "bidirectional"))
    )
    (net (code "94") (name "Net-(0_IO32-PadA)") (class "Default")
      (node (ref "0_IO32") (pin "A") (pinfunction "A_A") (pintype "passive"))
      (node (ref "U$32") (pin "P$2") (pinfunction "P$2_P$2") (pintype "bidirectional"))
    )
    (net (code "95") (name "Net-(1_D31-PadA)") (class "Default")
      (node (ref "1_D31") (pin "A") (pinfunction "A_A") (pintype "passive"))
      (node (ref "U$43") (pin "P$2") (pinfunction "P$2_P$2") (pintype "bidirectional"))
    )
    (net (code "96") (name "Net-(1_IO33-PadA)") (class "Default")
      (node (ref "1_IO33") (pin "A") (pinfunction "A_A") (pintype "passive"))
      (node (ref "U$33") (pin "P$2") (pinfunction "P$2_P$2") (pintype "bidirectional"))
    )
    (net (code "97") (name "Net-(2_D32-PadA)") (class "Default")
      (node (ref "2_D32") (pin "A") (pinfunction "A_A") (pintype "passive"))
      (node (ref "U$44") (pin "P$2") (pinfunction "P$2_P$2") (pintype "bidirectional"))
    )
    (net (code "98") (name "Net-(2_IO34-PadA)") (class "Default")
      (node (ref "2_IO34") (pin "A") (pinfunction "A_A") (pintype "passive"))
      (node (ref "U$34") (pin "P$2") (pinfunction "P$2_P$2") (pintype "bidirectional"))
    )
    (net (code "99") (name "Net-(3_D33-PadA)") (class "Default")
      (node (ref "3_D33") (pin "A") (pinfunction "A_A") (pintype "passive"))
      (node (ref "U$45") (pin "P$2") (pinfunction "P$2_P$2") (pintype "bidirectional"))
    )
    (net (code "100") (name "Net-(3_IO35-PadA)") (class "Default")
      (node (ref "3_IO35") (pin "A") (pinfunction "A_A") (pintype "passive"))
      (node (ref "U$35") (pin "P$2") (pinfunction "P$2_P$2") (pintype "bidirectional"))
    )
    (net (code "101") (name "Net-(AT-PadK)") (class "Default")
      (node (ref "AT") (pin "K") (pinfunction "K_K") (pintype "passive"))
      (node (ref "U$22") (pin "P$1") (pinfunction "P$1_P$1") (pintype "bidirectional"))
    )
    (net (code "102") (name "Net-(J1-Pad2)") (class "Default")
      (node (ref "J1") (pin "2") (pinfunction "2_2") (pintype "passive"))
      (node (ref "U$1") (pin "P$2") (pinfunction "P$2_P$2") (pintype "bidirectional"))
    )
    (net (code "103") (name "Net-(J1-Pad3)") (class "Default")
      (node (ref "J1") (pin "3") (pinfunction "3_3") (pintype "passive"))
      (node (ref "U$1") (pin "P$1") (pinfunction "P$1_P$1") (pintype "bidirectional"))
    )
    (net (code "104") (name "Net-(J2-Pad2)") (class "Default")
      (node (ref "J2") (pin "2") (pinfunction "2_2") (pintype "passive"))
      (node (ref "U$9") (pin "P$2") (pinfunction "P$2_P$2") (pintype "bidirectional"))
    )
    (net (code "105") (name "Net-(J2-Pad3)") (class "Default")
      (node (ref "J2") (pin "3") (pinfunction "3_3") (pintype "passive"))
      (node (ref "U$9") (pin "P$1") (pinfunction "P$1_P$1") (pintype "bidirectional"))
    )
    (net (code "106") (name "Net-(JYRO_RST-PadA)") (class "Default")
      (node (ref "JYRO_RST") (pin "A") (pinfunction "A_A") (pintype "passive"))
      (node (ref "U$70") (pin "3") (pinfunction "3_3") (pintype "bidirectional"))
      (node (ref "U$70") (pin "4") (pinfunction "4_4") (pintype "bidirectional"))
    )
    (net (code "107") (name "Net-(LED1-PadA)") (class "Default")
      (node (ref "LED1") (pin "A") (pinfunction "A_A") (pintype "passive"))
      (node (ref "U$19") (pin "P$2") (pinfunction "P$2_P$2") (pintype "bidirectional"))
    )
    (net (code "108") (name "Net-(LED18-PadA)") (class "Default")
      (node (ref "LED18") (pin "A") (pinfunction "A_A") (pintype "passive"))
      (node (ref "U$67") (pin "P$2") (pinfunction "P$2_P$2") (pintype "bidirectional"))
    )
    (net (code "109") (name "Net-(LED21-PadA)") (class "Default")
      (node (ref "LED21") (pin "A") (pinfunction "A_A") (pintype "passive"))
      (node (ref "U$23") (pin "P$2") (pinfunction "P$2_P$2") (pintype "bidirectional"))
    )
    (net (code "110") (name "Net-(LED22-PadA)") (class "Default")
      (node (ref "LED22") (pin "A") (pinfunction "A_A") (pintype "passive"))
      (node (ref "U$24") (pin "P$2") (pinfunction "P$2_P$2") (pintype "bidirectional"))
    )
    (net (code "111") (name "Net-(LED23-PadA)") (class "Default")
      (node (ref "LED23") (pin "A") (pinfunction "A_A") (pintype "passive"))
      (node (ref "U$73") (pin "P$2") (pinfunction "P$2_P$2") (pintype "bidirectional"))
    )
    (net (code "112") (name "Net-(LED24-PadA)") (class "Default")
      (node (ref "LED24") (pin "A") (pinfunction "A_A") (pintype "passive"))
      (node (ref "U$74") (pin "P$2") (pinfunction "P$2_P$2") (pintype "bidirectional"))
    )
    (net (code "113") (name "Net-(LED25-PadA)") (class "Default")
      (node (ref "LED25") (pin "A") (pinfunction "A_A") (pintype "passive"))
      (node (ref "U$75") (pin "P$2") (pinfunction "P$2_P$2") (pintype "bidirectional"))
    )
    (net (code "114") (name "Net-(LED26-PadA)") (class "Default")
      (node (ref "LED26") (pin "A") (pinfunction "A_A") (pintype "passive"))
      (node (ref "U$76") (pin "P$2") (pinfunction "P$2_P$2") (pintype "bidirectional"))
    )
    (net (code "115") (name "Net-(LED27-PadA)") (class "Default")
      (node (ref "LED27") (pin "A") (pinfunction "A_A") (pintype "passive"))
      (node (ref "U$77") (pin "P$2") (pinfunction "P$2_P$2") (pintype "bidirectional"))
    )
    (net (code "116") (name "Net-(Q1-G)") (class "Default")
      (node (ref "Q1") (pin "1") (pinfunction "G_1") (pintype "passive"))
      (node (ref "Q2") (pin "2") (pinfunction "S_2") (pintype "passive"))
      (node (ref "U$9") (pin "P$4") (pinfunction "P$4_P$4") (pintype "bidirectional"))
    )
    (net (code "117") (name "Net-(Q1-S)") (class "Default")
      (node (ref "Q1") (pin "2") (pinfunction "S_2") (pintype "passive"))
      (node (ref "Q2") (pin "1") (pinfunction "G_1") (pintype "passive"))
      (node (ref "U$9") (pin "P$6") (pinfunction "P$6_P$6") (pintype "bidirectional"))
    )
    (net (code "118") (name "Net-(U$2-2)") (class "Default")
      (node (ref "U$1") (pin "P$6") (pinfunction "P$6_P$6") (pintype "bidirectional"))
      (node (ref "U$2") (pin "P$2") (pinfunction "2_P$2") (pintype "bidirectional"))
    )
    (net (code "119") (name "Net-(U$3-2)") (class "Default")
      (node (ref "U$1") (pin "P$10") (pinfunction "P$10_P$10") (pintype "bidirectional"))
      (node (ref "U$3") (pin "P$2") (pinfunction "2_P$2") (pintype "bidirectional"))
    )
    (net (code "120") (name "Net-(U$20-2)") (class "Default")
      (node (ref "START_LED") (pin "K") (pinfunction "K_K") (pintype "passive"))
      (node (ref "U$20") (pin "P$3") (pinfunction "2_P$3") (pintype "bidirectional"))
    )
    (net (code "121") (name "Net-(U$22-P$3)") (class "Default")
      (node (ref "BL") (pin "K") (pinfunction "K_K") (pintype "passive"))
      (node (ref "U$22") (pin "P$2") (pinfunction "P$3_P$2") (pintype "bidirectional"))
    )
    (net (code "122") (name "Net-(U$26-P$3)") (class "Default")
      (node (ref "U$26") (pin "P$2") (pinfunction "P$3_P$2") (pintype "bidirectional"))
      (node (ref "Ⅰ_B") (pin "K") (pinfunction "K_K") (pintype "passive"))
    )
    (net (code "123") (name "Net-(U$26-PadP$1)") (class "Default")
      (node (ref "U$26") (pin "P$1") (pinfunction "P$1_P$1") (pintype "bidirectional"))
      (node (ref "Ⅰ_A") (pin "K") (pinfunction "K_K") (pintype "passive"))
    )
    (net (code "124") (name "Net-(U$27-P$3)") (class "Default")
      (node (ref "U$27") (pin "P$2") (pinfunction "P$3_P$2") (pintype "bidirectional"))
      (node (ref "Ⅱ_B") (pin "K") (pinfunction "K_K") (pintype "passive"))
    )
    (net (code "125") (name "Net-(U$27-PadP$1)") (class "Default")
      (node (ref "U$27") (pin "P$1") (pinfunction "P$1_P$1") (pintype "bidirectional"))
      (node (ref "Ⅱ_A") (pin "K") (pinfunction "K_K") (pintype "passive"))
    )
    (net (code "126") (name "Net-(U$36-PadP$1)") (class "Default")
      (node (ref "U$36") (pin "P$1") (pinfunction "P$1_P$1") (pintype "bidirectional"))
      (node (ref "W_C_ON") (pin "K") (pinfunction "K_K") (pintype "passive"))
    )
    (net (code "127") (name "Net-(U$41-1)") (class "Default")
      (node (ref "U$41") (pin "P$1") (pinfunction "1_P$1") (pintype "bidirectional"))
      (node (ref "U5") (pin "98") (pinfunction "AREF_98") (pintype "input"))
    )
    (net (code "128") (name "Net-(U$63-2)") (class "Default")
      (node (ref "U$63") (pin "P$2") (pinfunction "2_P$2") (pintype "bidirectional"))
      (node (ref "U$66") (pin "P$4") (pinfunction "P$4_P$4") (pintype "bidirectional"))
    )
    (net (code "129") (name "Net-(U$65-1)") (class "Default")
      (node (ref "U$65") (pin "P$1") (pinfunction "1_P$1") (pintype "bidirectional"))
      (node (ref "U4") (pin "20") (pinfunction "AREF_20") (pintype "input"))
    )
    (net (code "130") (name "Net-(U$66-PadP$2)") (class "Default")
      (node (ref "U$66") (pin "P$2") (pinfunction "P$2_P$2") (pintype "bidirectional"))
      (node (ref "U$69") (pin "P$1") (pinfunction "P$1_P$1") (pintype "bidirectional"))
    )
    (net (code "131") (name "Net-(U$69-P$4)") (class "Default")
      (node (ref "U$66") (pin "P$3") (pinfunction "P$3_P$3") (pintype "bidirectional"))
      (node (ref "U$69") (pin "P$6") (pinfunction "P$4_P$6") (pintype "bidirectional"))
    )
    (net (code "132") (name "Net-(U$70-LED+)") (class "Default")
      (node (ref "U$70") (pin "+") (pinfunction "LED+_+") (pintype "bidirectional"))
      (node (ref "U$71") (pin "P$2") (pinfunction "P$2_P$2") (pintype "bidirectional"))
    )
    (net (code "133") (name "Net-(U$78-P$3)") (class "Default")
      (node (ref "0_D30") (pin "K") (pinfunction "K_K") (pintype "passive"))
      (node (ref "0_IO32") (pin "K") (pinfunction "K_K") (pintype "passive"))
      (node (ref "1_D31") (pin "K") (pinfunction "K_K") (pintype "passive"))
      (node (ref "1_IO33") (pin "K") (pinfunction "K_K") (pintype "passive"))
      (node (ref "2_D32") (pin "K") (pinfunction "K_K") (pintype "passive"))
      (node (ref "2_IO34") (pin "K") (pinfunction "K_K") (pintype "passive"))
      (node (ref "3_D33") (pin "K") (pinfunction "K_K") (pintype "passive"))
      (node (ref "3_IO35") (pin "K") (pinfunction "K_K") (pintype "passive"))
      (node (ref "LED1") (pin "K") (pinfunction "K_K") (pintype "passive"))
      (node (ref "LED21") (pin "K") (pinfunction "K_K") (pintype "passive"))
      (node (ref "LED22") (pin "K") (pinfunction "K_K") (pintype "passive"))
      (node (ref "LED23") (pin "K") (pinfunction "K_K") (pintype "passive"))
      (node (ref "LED24") (pin "K") (pinfunction "K_K") (pintype "passive"))
      (node (ref "LED25") (pin "K") (pinfunction "K_K") (pintype "passive"))
      (node (ref "LED26") (pin "K") (pinfunction "K_K") (pintype "passive"))
      (node (ref "LED27") (pin "K") (pinfunction "K_K") (pintype "passive"))
      (node (ref "U$78") (pin "P$2") (pinfunction "P$3_P$2") (pintype "bidirectional"))
    )
    (net (code "134") (name "Net-(U4-PB6)") (class "Default")
      (node (ref "U4") (pin "7") (pinfunction "PB6_7") (pintype "bidirectional"))
      (node (ref "Y2") (pin "1") (pinfunction "IN_1") (pintype "input"))
    )
    (net (code "135") (name "Net-(U4-PB7)") (class "Default")
      (node (ref "U4") (pin "8") (pinfunction "PB7_8") (pintype "bidirectional"))
      (node (ref "Y2") (pin "3") (pinfunction "OUT_3") (pintype "output"))
    )
    (net (code "136") (name "Net-(U4-PD0)") (class "Default")
      (node (ref "U$69") (pin "P$5") (pinfunction "P$5_P$5") (pintype "bidirectional"))
      (node (ref "U4") (pin "30") (pinfunction "PD0_30") (pintype "bidirectional"))
    )
    (net (code "137") (name "Net-(U4-PD1)") (class "Default")
      (node (ref "U$69") (pin "P$2") (pinfunction "P$2_P$2") (pintype "bidirectional"))
      (node (ref "U4") (pin "31") (pinfunction "PD1_31") (pintype "bidirectional"))
    )
    (net (code "138") (name "RES") (class "Default")
      (node (ref "U$2") (pin "P$1") (pinfunction "1_P$1") (pintype "bidirectional"))
      (node (ref "U$4") (pin "P$1") (pinfunction "P$1_P$1") (pintype "bidirectional"))
      (node (ref "U$6") (pin "P$2") (pinfunction "P$2_P$2") (pintype "bidirectional"))
      (node (ref "U$6") (pin "P$3") (pinfunction "P$2_P$3") (pintype "bidirectional"))
      (node (ref "U5") (pin "30") (pinfunction "~{RESET}_30") (pintype "input"))
    )
    (net (code "139") (name "RX0") (class "Default")
      (node (ref "U$1") (pin "P$8") (pinfunction "P$8_P$8") (pintype "bidirectional"))
      (node (ref "U5") (pin "2") (pinfunction "(RXD0/PCINT8)_PE0_2") (pintype "input"))
    )
    (net (code "140") (name "RX1") (class "Default")
      (node (ref "Q3") (pin "2") (pinfunction "S_2") (pintype "passive"))
      (node (ref "Q3") (pin "3") (pinfunction "D_3") (pintype "passive"))
      (node (ref "U$14") (pin "P$3") (pinfunction "P$3_P$3") (pintype "bidirectional"))
      (node (ref "U$15") (pin "P$1") (pinfunction "P$1_P$1") (pintype "bidirectional"))
      (node (ref "U$16") (pin "P$1") (pinfunction "P$1_P$1") (pintype "bidirectional"))
      (node (ref "U5") (pin "45") (pinfunction "(RXD1/INT2)_PD2_45") (pintype "input"))
    )
    (net (code "141") (name "RX3") (class "Default")
      (node (ref "U$69") (pin "P$3") (pinfunction "P$3_P$3") (pintype "bidirectional"))
    )
    (net (code "142") (name "SCK") (class "Default")
      (node (ref "U$54") (pin "P$6") (pinfunction "SCK_P$6") (pintype "bidirectional"))
      (node (ref "U$55") (pin "P$6") (pinfunction "SCK_P$6") (pintype "bidirectional"))
      (node (ref "U$56") (pin "P$6") (pinfunction "SCK_P$6") (pintype "bidirectional"))
      (node (ref "U$57") (pin "P$6") (pinfunction "SCK_P$6") (pintype "bidirectional"))
      (node (ref "U$58") (pin "P$6") (pinfunction "SCK_P$6") (pintype "bidirectional"))
      (node (ref "U$59") (pin "P$6") (pinfunction "SCK_P$6") (pintype "bidirectional"))
      (node (ref "U$60") (pin "P$6") (pinfunction "SCK_P$6") (pintype "bidirectional"))
      (node (ref "U5") (pin "20") (pinfunction "(SCK/PCINT1)_PB1_20") (pintype "input"))
    )
    (net (code "143") (name "SCL") (class "Default")
      (node (ref "U$68") (pin "P$9") (pinfunction "SCL_P$9") (pintype "bidirectional"))
      (node (ref "U5") (pin "43") (pinfunction "(SCL/INT0)_PD0_43") (pintype "input"))
    )
    (net (code "144") (name "SCL_328") (class "Default")
      (node (ref "U$25") (pin "P$3") (pinfunction "SCL_P$3") (pintype "bidirectional"))
      (node (ref "U4") (pin "28") (pinfunction "PC5_28") (pintype "bidirectional"))
    )
    (net (code "145") (name "SDA") (class "Default")
      (node (ref "U$68") (pin "P$10") (pinfunction "SDA_P$10") (pintype "bidirectional"))
      (node (ref "U5") (pin "44") (pinfunction "(SDA/INT1)_PD1_44") (pintype "input"))
    )
    (net (code "146") (name "SDA_328") (class "Default")
      (node (ref "U$25") (pin "P$4") (pinfunction "SDA_P$4") (pintype "bidirectional"))
      (node (ref "U4") (pin "27") (pinfunction "PC4_27") (pintype "bidirectional"))
    )
    (net (code "147") (name "SS") (class "Default")
      (node (ref "U$54") (pin "P$3") (pinfunction "SS_P$3") (pintype "bidirectional"))
      (node (ref "U5") (pin "19") (pinfunction "(~{SS/PCINT0})_PB0_19") (pintype "input"))
    )
    (net (code "148") (name "TX0") (class "Default")
      (node (ref "U$1") (pin "P$9") (pinfunction "P$9_P$9") (pintype "bidirectional"))
      (node (ref "U5") (pin "3") (pinfunction "(TXD0)_PE1_3") (pintype "bidirectional"))
    )
    (net (code "149") (name "TX1") (class "Default")
      (node (ref "Q4") (pin "2") (pinfunction "S_2") (pintype "passive"))
      (node (ref "Q4") (pin "3") (pinfunction "D_3") (pintype "passive"))
      (node (ref "U$14") (pin "P$4") (pinfunction "P$6_P$4") (pintype "bidirectional"))
      (node (ref "U$17") (pin "P$1") (pinfunction "P$1_P$1") (pintype "bidirectional"))
      (node (ref "U$18") (pin "P$1") (pinfunction "P$1_P$1") (pintype "bidirectional"))
      (node (ref "U5") (pin "46") (pinfunction "(TXD1/INT3)_PD3_46") (pintype "input"))
    )
    (net (code "150") (name "TX3") (class "Default")
      (node (ref "U$69") (pin "P$4") (pinfunction "P$6_P$4") (pintype "bidirectional"))
    )
    (net (code "151") (name "XT1") (class "Default")
      (node (ref "U5") (pin "34") (pinfunction "XTAL1_34") (pintype "input"))
      (node (ref "Y4") (pin "1") (pinfunction "IN_1") (pintype "input"))
    )
    (net (code "152") (name "XT2") (class "Default")
      (node (ref "U5") (pin "33") (pinfunction "XTAL2_33") (pintype "output"))
      (node (ref "Y4") (pin "3") (pinfunction "OUT_3") (pintype "output"))
    )
    (net (code "153") (name "unconnected-(IC1-IO2-Pad24)") (class "Default")
      (node (ref "IC1") (pin "24") (pinfunction "IO2_24") (pintype "bidirectional"))
    )
    (net (code "154") (name "unconnected-(IC1-IO4-Pad26)") (class "Default")
      (node (ref "IC1") (pin "26") (pinfunction "IO4_26") (pintype "bidirectional"))
    )
    (net (code "155") (name "unconnected-(IC1-IO5-Pad29)") (class "Default")
      (node (ref "IC1") (pin "29") (pinfunction "IO5_29") (pintype "bidirectional"))
    )
    (net (code "156") (name "unconnected-(IC1-IO16-Pad27)") (class "Default")
      (node (ref "IC1") (pin "27") (pinfunction "IO16_27") (pintype "bidirectional"))
    )
    (net (code "157") (name "unconnected-(IC1-IO17-Pad28)") (class "Default")
      (node (ref "IC1") (pin "28") (pinfunction "IO17_28") (pintype "bidirectional"))
    )
    (net (code "158") (name "unconnected-(IC1-IO18-Pad30)") (class "Default")
      (node (ref "IC1") (pin "30") (pinfunction "IO18_30") (pintype "bidirectional"))
    )
    (net (code "159") (name "unconnected-(IC1-IO19-Pad31)") (class "Default")
      (node (ref "IC1") (pin "31") (pinfunction "IO19_31") (pintype "bidirectional"))
    )
    (net (code "160") (name "unconnected-(IC1-IO21-Pad33)") (class "Default")
      (node (ref "IC1") (pin "33") (pinfunction "IO21_33") (pintype "bidirectional"))
    )
    (net (code "161") (name "unconnected-(IC1-IO22-Pad36)") (class "Default")
      (node (ref "IC1") (pin "36") (pinfunction "IO22_36") (pintype "bidirectional"))
    )
    (net (code "162") (name "unconnected-(IC1-IO23-Pad37)") (class "Default")
      (node (ref "IC1") (pin "37") (pinfunction "IO23_37") (pintype "bidirectional"))
    )
    (net (code "163") (name "unconnected-(IC1-IO25-Pad10)") (class "Default")
      (node (ref "IC1") (pin "10") (pinfunction "IO25_10") (pintype "bidirectional"))
    )
    (net (code "164") (name "unconnected-(IC1-IO26-Pad11)") (class "Default")
      (node (ref "IC1") (pin "11") (pinfunction "IO26_11") (pintype "bidirectional"))
    )
    (net (code "165") (name "unconnected-(IC1-IO27-Pad12)") (class "Default")
      (node (ref "IC1") (pin "12") (pinfunction "IO27_12") (pintype "bidirectional"))
    )
    (net (code "166") (name "unconnected-(IC1-NC_1-Pad17)") (class "Default")
      (node (ref "IC1") (pin "17") (pinfunction "NC_1_17") (pintype "bidirectional"))
    )
    (net (code "167") (name "unconnected-(IC1-NC_2-Pad18)") (class "Default")
      (node (ref "IC1") (pin "18") (pinfunction "NC_2_18") (pintype "bidirectional"))
    )
    (net (code "168") (name "unconnected-(IC1-NC_3-Pad19)") (class "Default")
      (node (ref "IC1") (pin "19") (pinfunction "NC_3_19") (pintype "bidirectional"))
    )
    (net (code "169") (name "unconnected-(IC1-NC_4-Pad20)") (class "Default")
      (node (ref "IC1") (pin "20") (pinfunction "NC_4_20") (pintype "bidirectional"))
    )
    (net (code "170") (name "unconnected-(IC1-NC_5-Pad21)") (class "Default")
      (node (ref "IC1") (pin "21") (pinfunction "NC_5_21") (pintype "bidirectional"))
    )
    (net (code "171") (name "unconnected-(IC1-NC_6-Pad22)") (class "Default")
      (node (ref "IC1") (pin "22") (pinfunction "NC_6_22") (pintype "bidirectional"))
    )
    (net (code "172") (name "unconnected-(IC1-NC_7-Pad32)") (class "Default")
      (node (ref "IC1") (pin "32") (pinfunction "NC_7_32") (pintype "bidirectional"))
    )
    (net (code "173") (name "unconnected-(IC1-SENSOR_VN-Pad5)") (class "Default")
      (node (ref "IC1") (pin "5") (pinfunction "SENSOR_VN_5") (pintype "bidirectional"))
    )
    (net (code "174") (name "unconnected-(IC1-SENSOR_VP-Pad4)") (class "Default")
      (node (ref "IC1") (pin "4") (pinfunction "SENSOR_VP_4") (pintype "bidirectional"))
    )
    (net (code "175") (name "unconnected-(J1-Pad4)") (class "Default")
      (node (ref "J1") (pin "4") (pinfunction "4_4") (pintype "passive"))
    )
    (net (code "176") (name "unconnected-(J2-Pad4)") (class "Default")
      (node (ref "J2") (pin "4") (pinfunction "4_4") (pintype "passive"))
    )
    (net (code "177") (name "unconnected-(U$1-PadP$4)") (class "Default")
      (node (ref "U$1") (pin "P$4") (pinfunction "P$4_P$4") (pintype "bidirectional"))
    )
    (net (code "178") (name "unconnected-(U$1-PadP$5)") (class "Default")
      (node (ref "U$1") (pin "P$5") (pinfunction "P$5_P$5") (pintype "bidirectional"))
    )
    (net (code "179") (name "unconnected-(U$9-PadP$5)") (class "Default")
      (node (ref "U$9") (pin "P$5") (pinfunction "P$5_P$5") (pintype "bidirectional"))
    )
    (net (code "180") (name "unconnected-(U$20-3-PadP$4)") (class "Default")
      (node (ref "U$20") (pin "P$4") (pinfunction "3_P$4") (pintype "bidirectional"))
    )
    (net (code "181") (name "unconnected-(U$25-ADO-PadP$7)") (class "Default")
      (node (ref "U$25") (pin "P$7") (pinfunction "ADO_P$7") (pintype "bidirectional"))
    )
    (net (code "182") (name "unconnected-(U$25-INT-PadP$8)") (class "Default")
      (node (ref "U$25") (pin "P$8") (pinfunction "INT_P$8") (pintype "bidirectional"))
    )
    (net (code "183") (name "unconnected-(U$25-XCL-PadP$6)") (class "Default")
      (node (ref "U$25") (pin "P$6") (pinfunction "XCL_P$6") (pintype "bidirectional"))
    )
    (net (code "184") (name "unconnected-(U$25-XDA-PadP$5)") (class "Default")
      (node (ref "U$25") (pin "P$5") (pinfunction "XDA_P$5") (pintype "bidirectional"))
    )
    (net (code "185") (name "unconnected-(U$78-PadP$1)") (class "Default")
      (node (ref "U$78") (pin "P$1") (pinfunction "P$1_P$1") (pintype "bidirectional"))
    )
    (net (code "186") (name "unconnected-(U4-ADC6-Pad19)") (class "Default")
      (node (ref "U4") (pin "19") (pinfunction "ADC6_19") (pintype "bidirectional"))
    )
    (net (code "187") (name "unconnected-(U4-ADC7-Pad22)") (class "Default")
      (node (ref "U4") (pin "22") (pinfunction "ADC7_22") (pintype "bidirectional"))
    )
    (net (code "188") (name "unconnected-(U4-PC0-Pad23)") (class "Default")
      (node (ref "U4") (pin "23") (pinfunction "PC0_23") (pintype "bidirectional"))
    )
    (net (code "189") (name "unconnected-(U4-PC1-Pad24)") (class "Default")
      (node (ref "U4") (pin "24") (pinfunction "PC1_24") (pintype "bidirectional"))
    )
    (net (code "190") (name "unconnected-(U4-PC2-Pad25)") (class "Default")
      (node (ref "U4") (pin "25") (pinfunction "PC2_25") (pintype "bidirectional"))
    )
    (net (code "191") (name "unconnected-(U4-PC3-Pad26)") (class "Default")
      (node (ref "U4") (pin "26") (pinfunction "PC3_26") (pintype "bidirectional"))
    )
    (net (code "192") (name "unconnected-(U5-(CLKO{slash}ICP3{slash}INT7)_PE7-Pad9)") (class "Default")
      (node (ref "U5") (pin "9") (pinfunction "(CLKO/ICP3/INT7)_PE7_9") (pintype "input"))
    )
    (net (code "193") (name "unconnected-(U5-(ICP1)_PD4-Pad47)") (class "Default")
      (node (ref "U5") (pin "47") (pinfunction "(ICP1)_PD4_47") (pintype "bidirectional"))
    )
    (net (code "194") (name "unconnected-(U5-(T1)_PD6-Pad49)") (class "Default")
      (node (ref "U5") (pin "49") (pinfunction "(T1)_PD6_49") (pintype "bidirectional"))
    )
    (net (code "195") (name "unconnected-(U5-(T3{slash}INT6)_PE6-Pad8)") (class "Default")
      (node (ref "U5") (pin "8") (pinfunction "(T3/INT6)_PE6_8") (pintype "input"))
    )
    (net (code "196") (name "unconnected-(U5-(T4)_PH7-Pad27)") (class "Default")
      (node (ref "U5") (pin "27") (pinfunction "(T4)_PH7_27") (pintype "bidirectional"))
    )
    (net (code "197") (name "unconnected-(U5-(TOSC1)_PG4-Pad29)") (class "Default")
      (node (ref "U5") (pin "29") (pinfunction "(TOSC1)_PG4_29") (pintype "bidirectional"))
    )
    (net (code "198") (name "unconnected-(U5-(TOSC2)_PG3-Pad28)") (class "Default")
      (node (ref "U5") (pin "28") (pinfunction "(TOSC2)_PG3_28") (pintype "bidirectional"))
    )
    (net (code "199") (name "unconnected-(U5-(XCK0{slash}AIN0)_PE2-Pad4)") (class "Default")
      (node (ref "U5") (pin "4") (pinfunction "(XCK0/AIN0)_PE2_4") (pintype "input"))
    )
    (net (code "200") (name "unconnected-(U5-(XCK1)_PD5-Pad48)") (class "Default")
      (node (ref "U5") (pin "48") (pinfunction "(XCK1)_PD5_48") (pintype "bidirectional"))
    )
    (net (code "201") (name "unconnected-(U5-(XCK2)_PH2-Pad14)") (class "Default")
      (node (ref "U5") (pin "14") (pinfunction "(XCK2)_PH2_14") (pintype "bidirectional"))
    )
    (net (code "202") (name "unconnected-(U5-PJ2_(XCK3{slash}PCINT11)-Pad65)") (class "Default")
      (node (ref "U5") (pin "65") (pinfunction "PJ2_(XCK3/PCINT11)_65") (pintype "input"))
    )
    (net (code "203") (name "unconnected-(U5-PJ3_(PCINT12)-Pad66)") (class "Default")
      (node (ref "U5") (pin "66") (pinfunction "PJ3_(PCINT12)_66") (pintype "input"))
    )
    (net (code "204") (name "unconnected-(U5-PJ4_(PCINT13)-Pad67)") (class "Default")
      (node (ref "U5") (pin "67") (pinfunction "PJ4_(PCINT13)_67") (pintype "input"))
    )
    (net (code "205") (name "unconnected-(U5-PJ5_(PCINT14)-Pad68)") (class "Default")
      (node (ref "U5") (pin "68") (pinfunction "PJ5_(PCINT14)_68") (pintype "input"))
    )
    (net (code "206") (name "unconnected-(U5-PJ6_(PCINT15)-Pad69)") (class "Default")
      (node (ref "U5") (pin "69") (pinfunction "PJ6_(PCINT15)_69") (pintype "input"))
    )
    (net (code "207") (name "unconnected-(U5-PJ7-Pad79)") (class "Default")
      (node (ref "U5") (pin "79") (pinfunction "PJ7_79") (pintype "bidirectional"))
    )
  )
)
